# 1_P1.net
KiCad netlist of a schematic drawn in Altium Designer
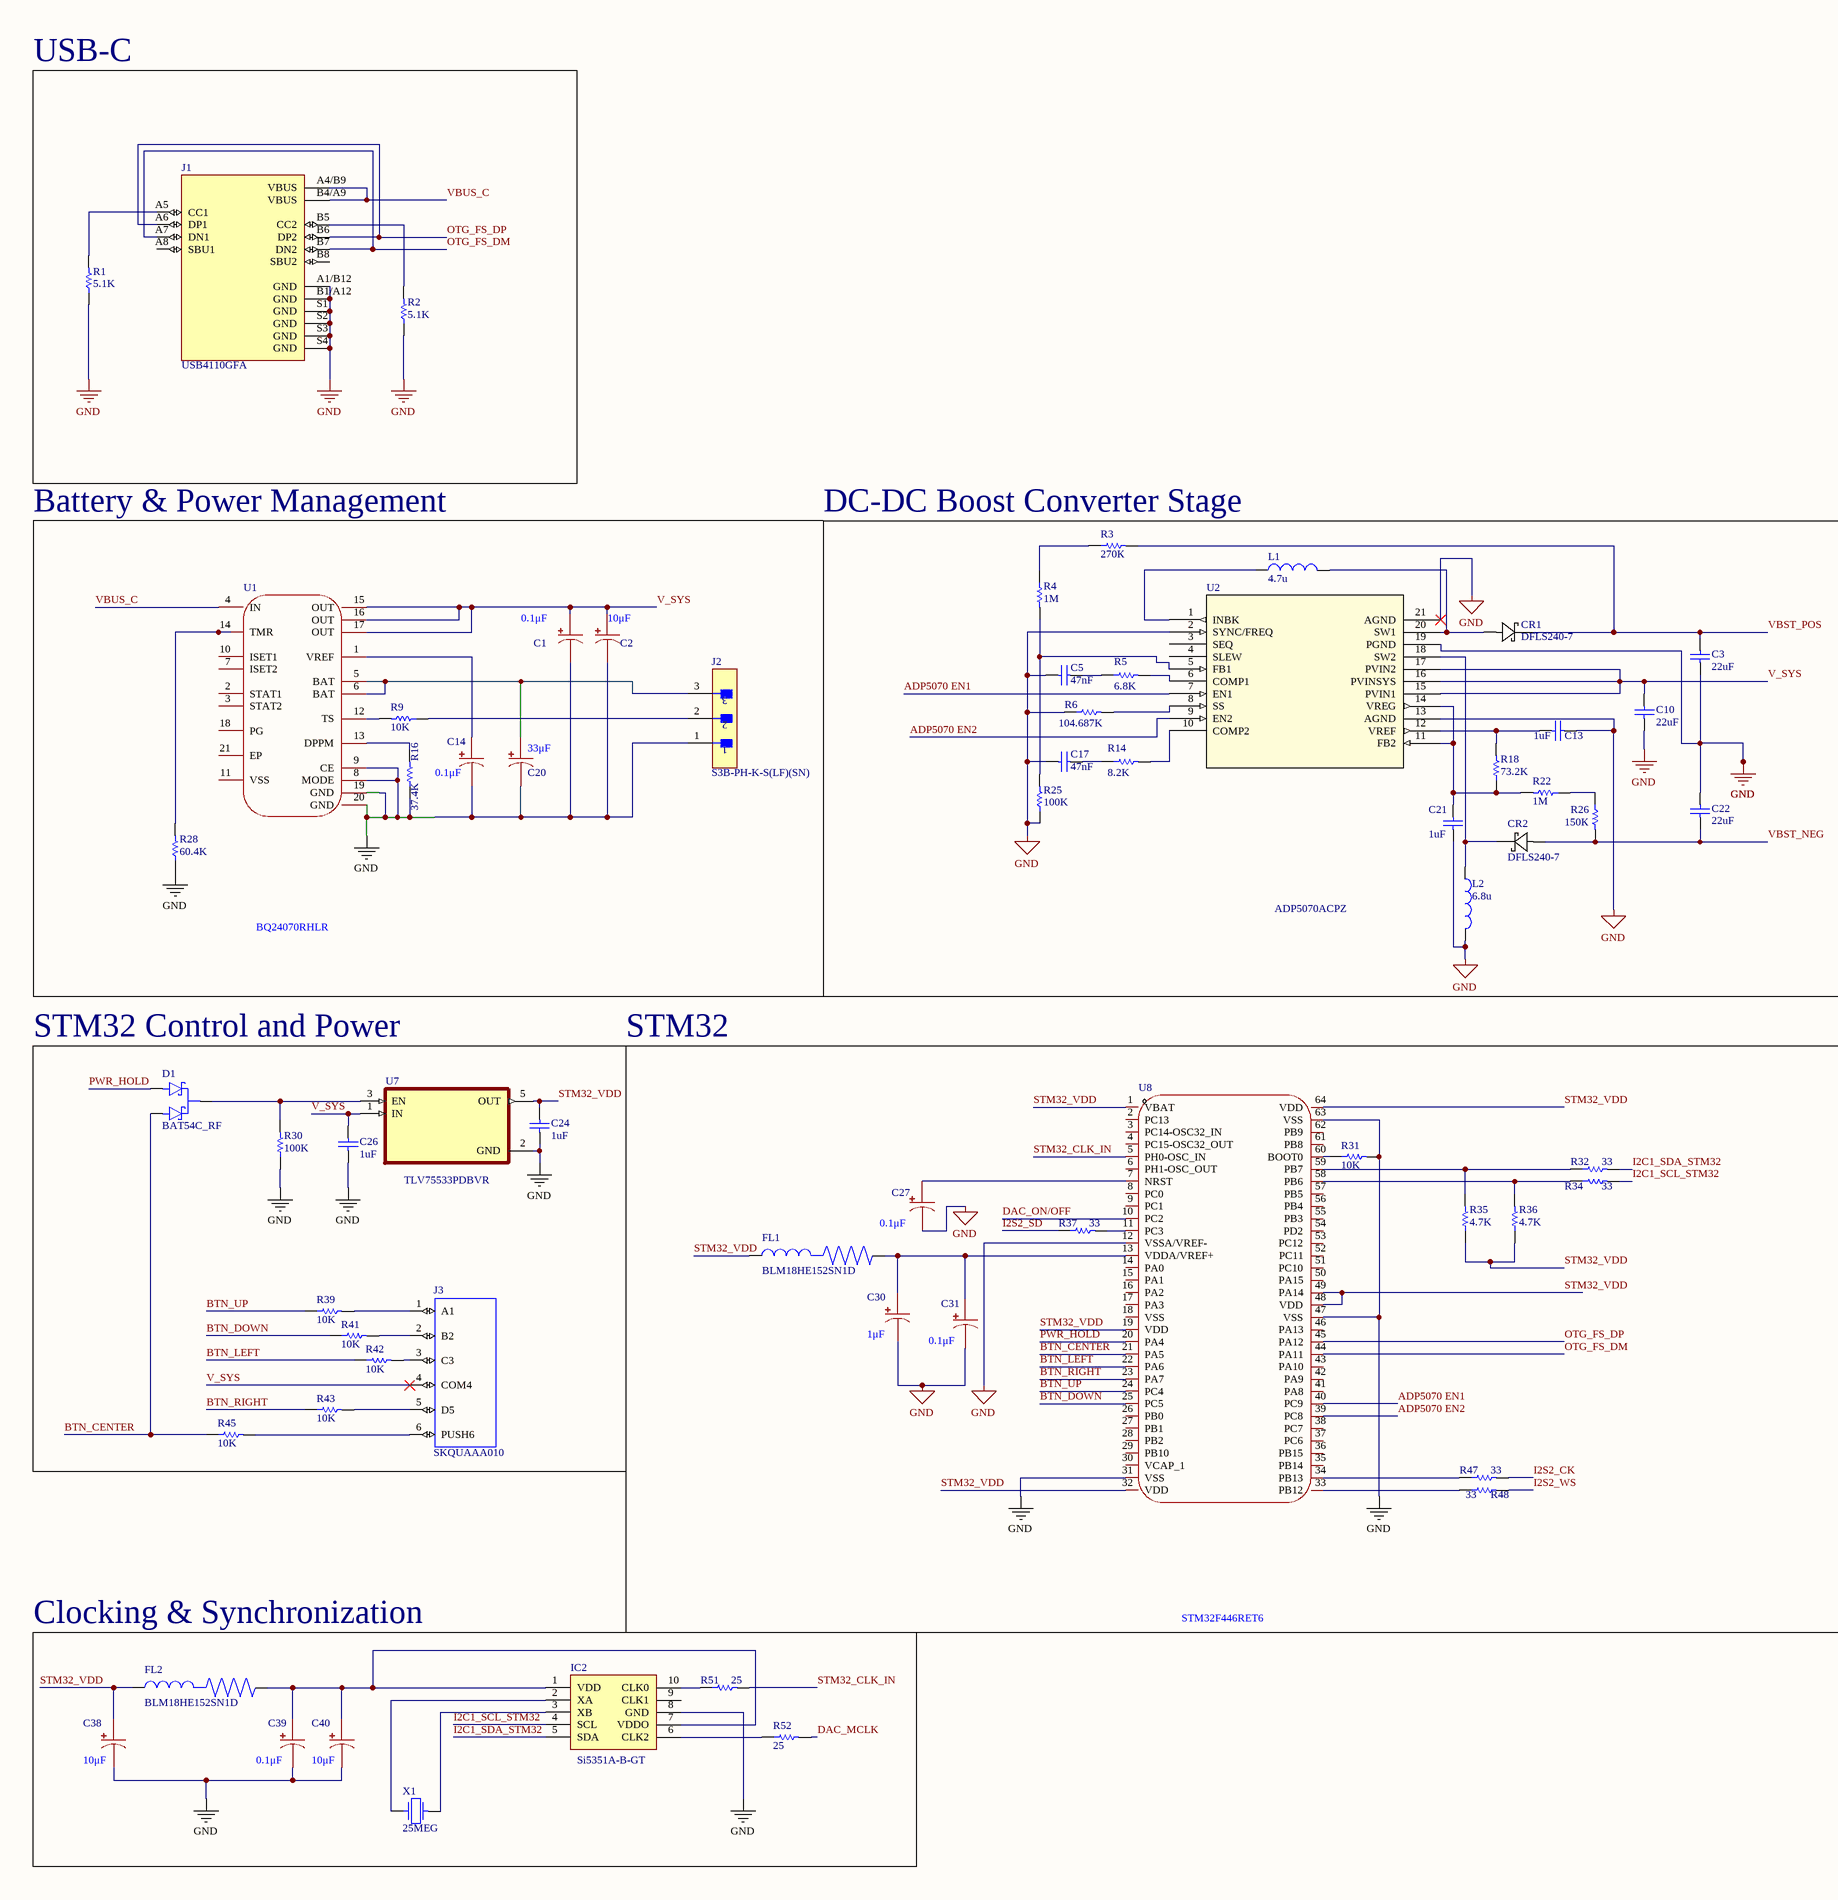
[diagram p0: 1_P1.schdoc, left]
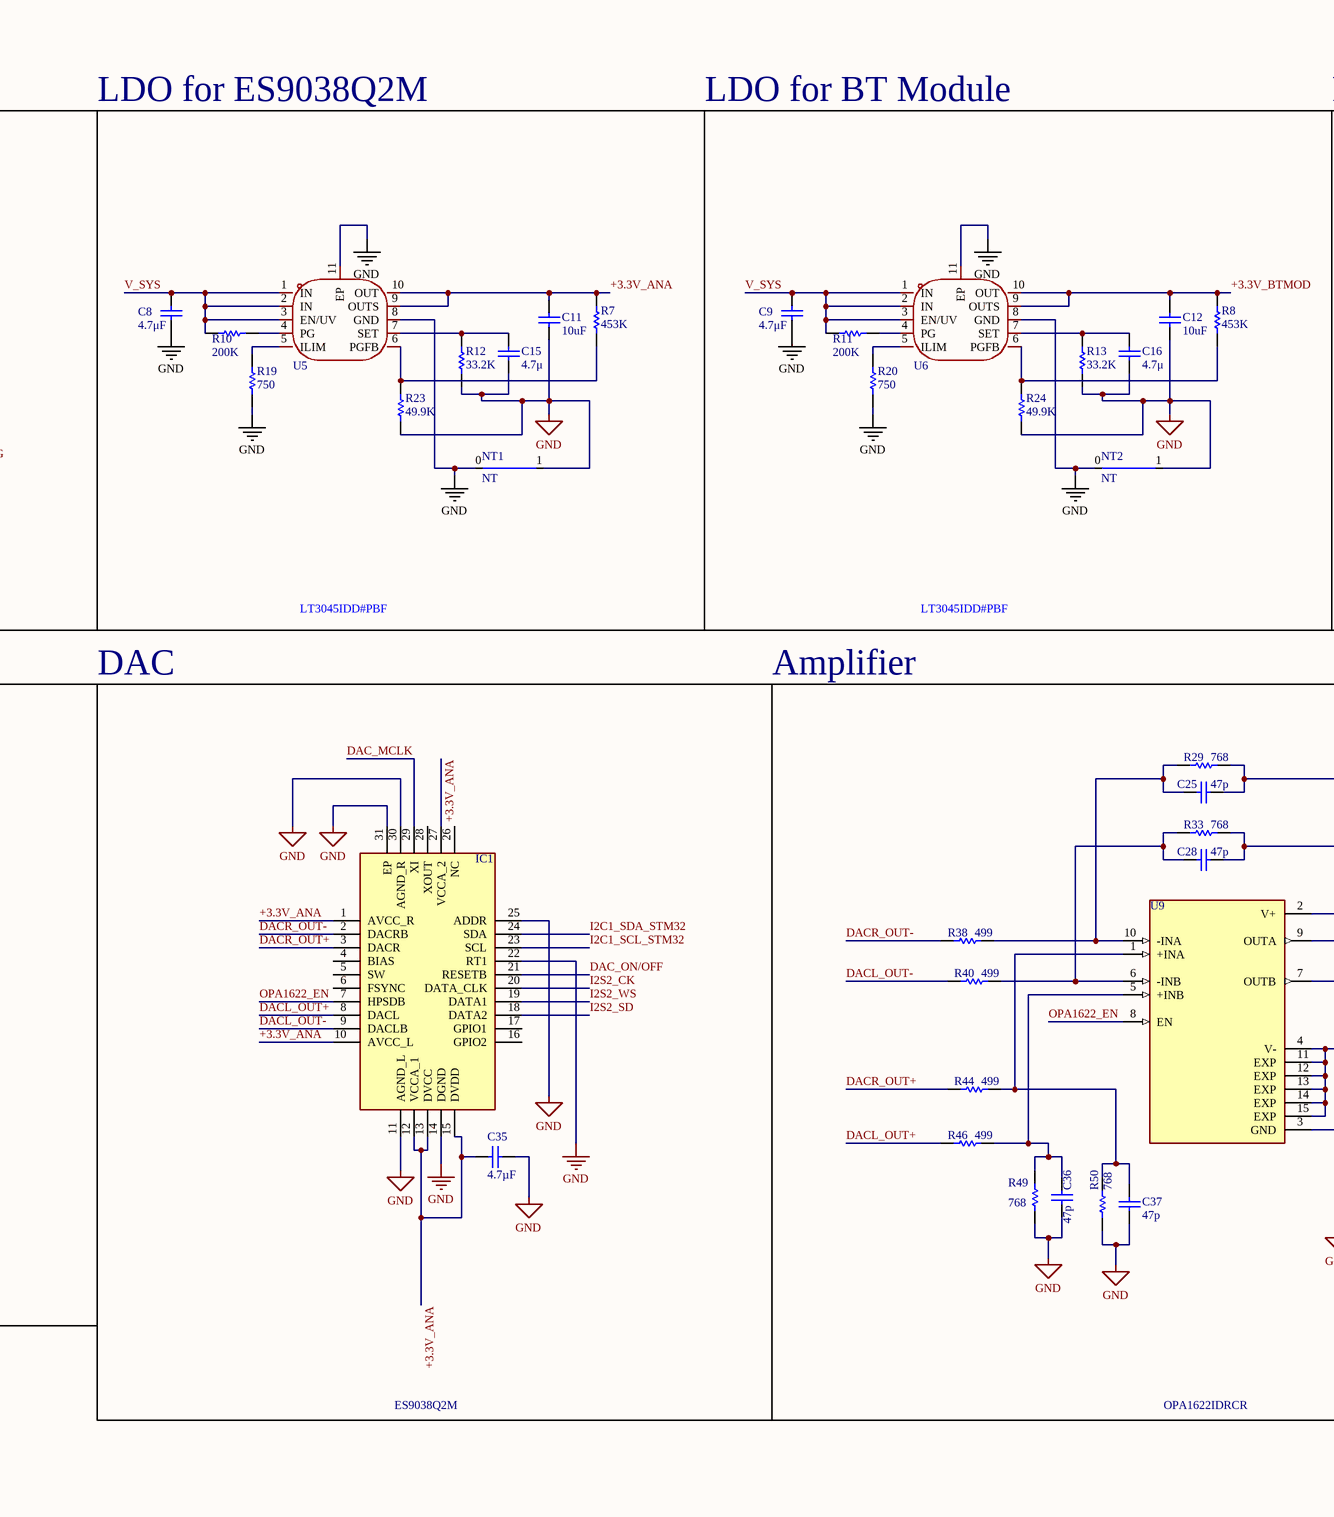
[diagram p1: 1_P1.schdoc, middle]
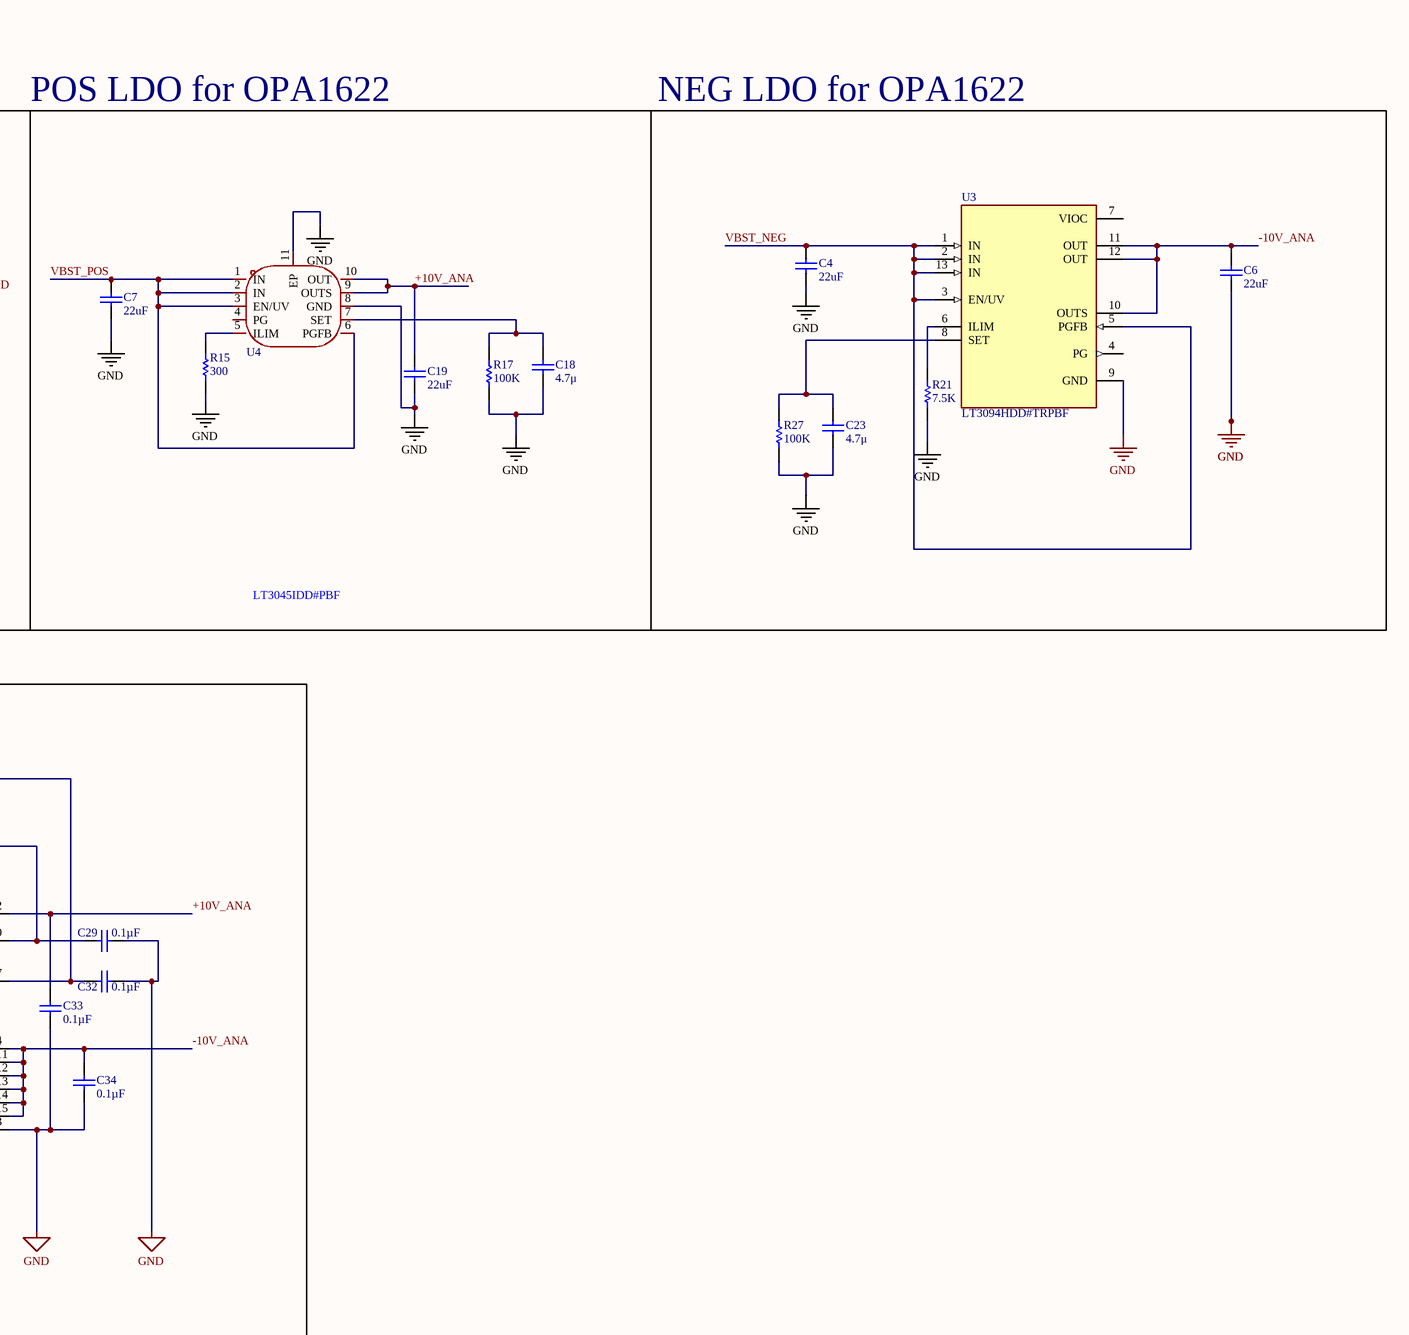
[diagram p2: 1_P1.schdoc, right]

(export (version "E")
  (design (tool "Eeschema 10.0.6"))
  (components
    (comp (ref "C1")
      (value "0.1μF")
      (footprint "FP-GRM155-0_05-MFG")
      (fields
        (field (name "MANUFACTURER") "Nichicon(尼吉康)")
        (field (name "MANUFACTURER PART") "UUG1J101MNQ1MS")
        (field (name "TOLERANCE") "±20%")
      )
      (libsource (lib "altium-import") (part "root_0_UUG1J101MNQ1MS_"))
    )
    (comp (ref "C2")
      (value "10μF")
      (footprint "CAPC2012X145N")
      (fields
        (field (name "MANUFACTURER") "Nichicon(尼吉康)")
        (field (name "MANUFACTURER PART") "UUG1J101MNQ1MS")
        (field (name "TOLERANCE") "±20%")
      )
      (libsource (lib "altium-import") (part "root_0_UUG1J101MNQ1MS_"))
    )
    (comp (ref "C3")
      (value "22uF")
      (footprint "FP-GRM32-MFG")
      (description "Capacitor")
      (libsource (lib "Simulation Generic Components") (part "Capacitor"))
    )
    (comp (ref "C4")
      (value "22uF")
      (footprint "FP-GRM32-MFG")
      (description "Capacitor")
      (libsource (lib "Simulation Generic Components") (part "Capacitor"))
    )
    (comp (ref "C5")
      (value "47nF")
      (footprint "FP-GRM155-0_05-MFG")
      (description "Capacitor")
      (libsource (lib "Simulation Generic Components") (part "Capacitor"))
    )
    (comp (ref "C6")
      (value "22uF")
      (footprint "FP-GRM32-MFG")
      (description "Capacitor")
      (libsource (lib "Simulation Generic Components") (part "Capacitor"))
    )
    (comp (ref "C7")
      (value "22uF")
      (footprint "FP-GRM32-MFG")
      (description "Capacitor")
      (libsource (lib "Simulation Generic Components") (part "Capacitor"))
    )
    (comp (ref "C8")
      (value "4.7μF")
      (footprint "CAPC1608X95N")
      (description "Capacitor")
      (libsource (lib "Simulation Generic Components") (part "Capacitor"))
    )
    (comp (ref "C9")
      (value "4.7μF")
      (footprint "CAPC1608X95N")
      (description "Capacitor")
      (libsource (lib "Simulation Generic Components") (part "Capacitor"))
    )
    (comp (ref "C10")
      (value "22uF")
      (footprint "FP-GRM32-MFG")
      (description "Capacitor")
      (libsource (lib "Simulation Generic Components") (part "Capacitor"))
    )
    (comp (ref "C11")
      (value "10uF")
      (footprint "FP-GRM32-MFG")
      (description "Capacitor")
      (libsource (lib "Simulation Generic Components") (part "Capacitor"))
    )
    (comp (ref "C12")
      (value "10uF")
      (footprint "FP-GRM32-MFG")
      (description "Capacitor")
      (libsource (lib "Simulation Generic Components") (part "Capacitor"))
    )
    (comp (ref "C13")
      (value "1uF")
      (footprint "CAPC1608X90N")
      (description "Capacitor")
      (libsource (lib "Simulation Generic Components") (part "Capacitor"))
    )
    (comp (ref "C14")
      (value "0.1μF")
      (footprint "FP-GRM155-0_05-MFG")
      (fields
        (field (name "MANUFACTURER") "Nichicon(尼吉康)")
        (field (name "MANUFACTURER PART") "UUG1J101MNQ1MS")
        (field (name "TOLERANCE") "±20%")
      )
      (libsource (lib "altium-import") (part "root_0_UUG1J101MNQ1MS_"))
    )
    (comp (ref "C15")
      (value "4.7μ")
      (footprint "FP-CL10-IPC_B")
      (description "Capacitor")
      (libsource (lib "Simulation Generic Components") (part "Capacitor"))
    )
    (comp (ref "C16")
      (value "4.7μ")
      (footprint "FP-CL10-IPC_B")
      (description "Capacitor")
      (libsource (lib "Simulation Generic Components") (part "Capacitor"))
    )
    (comp (ref "C17")
      (value "47nF")
      (footprint "FP-GRM155-0_05-MFG")
      (description "Capacitor")
      (libsource (lib "Simulation Generic Components") (part "Capacitor"))
    )
    (comp (ref "C18")
      (value "4.7μ")
      (footprint "FP-CL10-IPC_B")
      (description "Capacitor")
      (libsource (lib "Simulation Generic Components") (part "Capacitor"))
    )
    (comp (ref "C19")
      (value "22uF")
      (footprint "FP-GRM32-MFG")
      (description "Capacitor")
      (libsource (lib "Simulation Generic Components") (part "Capacitor"))
    )
    (comp (ref "C20")
      (value "33μF")
      (footprint "CAPMP7.6X4.3_3.1N_KEM")
      (fields
        (field (name "MANUFACTURER") "Nichicon(尼吉康)")
        (field (name "MANUFACTURER PART") "UUG1J101MNQ1MS")
        (field (name "TOLERANCE") "±20%")
      )
      (libsource (lib "altium-import") (part "root_0_UUG1J101MNQ1MS_"))
    )
    (comp (ref "C21")
      (value "1uF")
      (footprint "CAPC1608X90N")
      (description "Capacitor")
      (libsource (lib "Simulation Generic Components") (part "Capacitor"))
    )
    (comp (ref "C22")
      (value "22uF")
      (footprint "FP-GRM32-MFG")
      (description "Capacitor")
      (libsource (lib "Simulation Generic Components") (part "Capacitor"))
    )
    (comp (ref "C23")
      (value "4.7μ")
      (footprint "FP-CL10-IPC_B")
      (description "Capacitor")
      (libsource (lib "Simulation Generic Components") (part "Capacitor"))
    )
    (comp (ref "C24")
      (value "1uF")
      (footprint "CAPC1608X90N")
      (description "Capacitor")
      (libsource (lib "Simulation Generic Components") (part "Capacitor"))
    )
    (comp (ref "C25")
      (value "47p")
      (footprint "FP-GCM155-0_05-MFG")
      (description "Capacitor")
      (libsource (lib "Simulation Generic Components") (part "Capacitor"))
    )
    (comp (ref "C26")
      (value "1uF")
      (footprint "CAPC1608X90N")
      (description "Capacitor")
      (libsource (lib "Simulation Generic Components") (part "Capacitor"))
    )
    (comp (ref "C27")
      (value "0.1μF")
      (footprint "FP-GRM155-0_05-MFG")
      (fields
        (field (name "MANUFACTURER") "Nichicon(尼吉康)")
        (field (name "MANUFACTURER PART") "UUG1J101MNQ1MS")
        (field (name "TOLERANCE") "±20%")
      )
      (libsource (lib "altium-import") (part "root_0_UUG1J101MNQ1MS_"))
    )
    (comp (ref "C28")
      (value "47p")
      (footprint "FP-GCM155-0_05-MFG")
      (description "Capacitor")
      (libsource (lib "Simulation Generic Components") (part "Capacitor"))
    )
    (comp (ref "C29")
      (value "0.1µF")
      (footprint "FP-GRM155-0_05-MFG")
      (description "Capacitor")
      (libsource (lib "Simulation Generic Components") (part "Capacitor"))
    )
    (comp (ref "C30")
      (value "1μF")
      (footprint "FP-C0402C-BB-MFG")
      (fields
        (field (name "MANUFACTURER") "Nichicon(尼吉康)")
        (field (name "MANUFACTURER PART") "UUG1J101MNQ1MS")
        (field (name "TOLERANCE") "±20%")
      )
      (libsource (lib "altium-import") (part "root_0_UUG1J101MNQ1MS_"))
    )
    (comp (ref "C31")
      (value "0.1μF")
      (footprint "FP-GRM155-0_05-MFG")
      (fields
        (field (name "MANUFACTURER") "Nichicon(尼吉康)")
        (field (name "MANUFACTURER PART") "UUG1J101MNQ1MS")
        (field (name "TOLERANCE") "±20%")
      )
      (libsource (lib "altium-import") (part "root_0_UUG1J101MNQ1MS_"))
    )
    (comp (ref "C32")
      (value "0.1µF")
      (footprint "FP-GRM155-0_05-MFG")
      (description "Capacitor")
      (libsource (lib "Simulation Generic Components") (part "Capacitor"))
    )
    (comp (ref "C33")
      (value "0.1µF")
      (footprint "FP-GRM155-0_05-MFG")
      (description "Capacitor")
      (libsource (lib "Simulation Generic Components") (part "Capacitor"))
    )
    (comp (ref "C34")
      (value "0.1µF")
      (footprint "FP-GRM155-0_05-MFG")
      (description "Capacitor")
      (libsource (lib "Simulation Generic Components") (part "Capacitor"))
    )
    (comp (ref "C35")
      (value "4.7µF")
      (footprint "FP-CL10-IPC_B")
      (description "Capacitor")
      (libsource (lib "Simulation Generic Components") (part "Capacitor"))
    )
    (comp (ref "C36")
      (value "47p")
      (footprint "FP-GCM155-0_05-MFG")
      (description "Capacitor")
      (libsource (lib "Simulation Generic Components") (part "Capacitor"))
    )
    (comp (ref "C37")
      (value "47p")
      (footprint "FP-GCM155-0_05-MFG")
      (description "Capacitor")
      (libsource (lib "Simulation Generic Components") (part "Capacitor"))
    )
    (comp (ref "C38")
      (value "10μF")
      (footprint "FP-CL21B106KOQNNNE-MFG")
      (fields
        (field (name "MANUFACTURER") "Nichicon(尼吉康)")
        (field (name "MANUFACTURER PART") "UUG1J101MNQ1MS")
        (field (name "TOLERANCE") "±20%")
      )
      (libsource (lib "altium-import") (part "root_0_UUG1J101MNQ1MS_"))
    )
    (comp (ref "C39")
      (value "0.1μF")
      (footprint "FP-GRM155-0_05-MFG")
      (fields
        (field (name "MANUFACTURER") "Nichicon(尼吉康)")
        (field (name "MANUFACTURER PART") "UUG1J101MNQ1MS")
        (field (name "TOLERANCE") "±20%")
      )
      (libsource (lib "altium-import") (part "root_0_UUG1J101MNQ1MS_"))
    )
    (comp (ref "C40")
      (value "10μF")
      (footprint "FP-CL21B106KOQNNNE-MFG")
      (fields
        (field (name "MANUFACTURER") "Nichicon(尼吉康)")
        (field (name "MANUFACTURER PART") "UUG1J101MNQ1MS")
        (field (name "TOLERANCE") "±20%")
      )
      (libsource (lib "altium-import") (part "root_0_UUG1J101MNQ1MS_"))
    )
    (comp (ref "CR1")
      (value "DFLS240-7")
      (footprint "POWERDI123_DIO")
      (description "Description")
      (fields (field (name "COPYRIGHT") "Copyright (C) 2026 Ultra Librarian. All rights reserved."))
      (libsource (lib "DFLS240-7") (part "DFLS240-7"))
    )
    (comp (ref "CR2")
      (value "DFLS240-7")
      (footprint "POWERDI123_DIO")
      (description "Description")
      (fields (field (name "COPYRIGHT") "Copyright (C) 2026 Ultra Librarian. All rights reserved."))
      (libsource (lib "DFLS240-7") (part "DFLS240-7"))
    )
    (comp (ref "D1")
      (value "BAT54C_RF")
      (footprint "SOT95P237X112-3N")
      (description "SOT-23, 30V, 0.2A, Schottky Diode")
      (fields (field (name "MF") "Taiwan Semiconductor") (field (name "MP") "BAT54C RF"))
      (libsource (lib "BAT54C_RF") (part "BAT54C_RF"))
    )
    (comp (ref "FL1")
      (value "BLM18HE152SN1D")
      (footprint "FP-BLM18-0_15-t0_8-MFG")
      (description "1.5 kOhms @ 100MHz 1 Signal Line Ferrite Bead 0603 (1608 Metric) 500mA 500mOhm")
      (fields (field (name "MF") "Murata Electronics"))
      (libsource (lib "BLM18HE152SN1D") (part "BLM18HE152SN1D"))
    )
    (comp (ref "FL2")
      (value "BLM18HE152SN1D")
      (footprint "FP-BLM18-0_15-t0_8-MFG")
      (description "1.5 kOhms @ 100MHz 1 Signal Line Ferrite Bead 0603 (1608 Metric) 500mA 500mOhm")
      (fields (field (name "MF") "Murata Electronics"))
      (libsource (lib "BLM18HE152SN1D") (part "BLM18HE152SN1D"))
    )
    (comp (ref "IC1")
      (value "ES9038Q2M")
      (footprint "SamacSys:QFN40P300X500X80-31N-D")
      (description "Integrated Circuit")
      (fields (field (name "MOUSER PART NUMBER") "460-ES9038Q2M"))
      (libsource (lib "*") (part "ES9038Q2M"))
    )
    (comp (ref "IC2")
      (value "Si5351A-B-GT")
      (footprint "SamacSys:SOP50P490X110-10N")
      (description "Integrated Circuit")
      (fields
        (field (name "MOUSER PART NUMBER") "634-SI5351A-B-GT")
        (field (name "ARROW PART NUMBER") "SI5351A-B-GT")
      )
      (libsource (lib "*") (part "Si5351A-B-GT"))
    )
    (comp (ref "J1")
      (value "USB4110GFA")
      (footprint "GCT_USB4110GFA")
      (fields (field (name "MF") "Global Connector Technology"))
      (libsource (lib "USB4110GFA") (part "USB4110GFA"))
    )
    (comp (ref "J2")
      (value "S3B-PH-K-S(LF)(SN)")
      (footprint "FP-S3B-PH-K-S_LF_SN-MFG")
      (description "CONN HEADER R/A 3POS 2MM")
      (libsource (lib "Altium Content Vault") (part "0d3f023dd272f625e17a2be33dea85f"))
    )
    (comp (ref "J3")
      (value "SKQUAAA010")
      (footprint "SKQUAAA010")
      (libsource (lib "SKQUAAA010") (part "SKQUAAA010"))
    )
    (comp (ref "L1")
      (value "4.7u")
      (footprint "WE-MAPI_4030")
      (description "Inductor")
      (libsource (lib "Simulation Generic Components") (part "Inductor"))
    )
    (comp (ref "L2")
      (value "6.8u")
      (footprint "WE-MAPI_4030")
      (description "Inductor")
      (libsource (lib "Simulation Generic Components") (part "Inductor"))
    )
    (comp (ref "NT1")
      (value "NT")
      (footprint "NETTIE_SMD")
      (description "Net Tie SMD")
      (libsource (lib "Integrated_Library1") (part "NetTie_SMD"))
    )
    (comp (ref "NT2")
      (value "NT")
      (footprint "NETTIE_SMD")
      (description "Net Tie SMD")
      (libsource (lib "Integrated_Library1") (part "NetTie_SMD"))
    )
    (comp (ref "R1")
      (value "5.1K")
      (footprint "RESC1005X40X25NL05T10")
      (description "Resistor")
      (libsource (lib "Simulation Generic Components") (part "Resistor"))
    )
    (comp (ref "R2")
      (value "5.1K")
      (footprint "RESC1005X40X25NL05T10")
      (description "Resistor")
      (libsource (lib "Simulation Generic Components") (part "Resistor"))
    )
    (comp (ref "R3")
      (value "270К")
      (footprint "RES_RS73F_2B_KOA")
      (description "Resistor")
      (libsource (lib "Simulation Generic Components") (part "Resistor"))
    )
    (comp (ref "R4")
      (value "1M")
      (footprint "RESC3216X70X50NL20T25")
      (description "Resistor")
      (libsource (lib "Simulation Generic Components") (part "Resistor"))
    )
    (comp (ref "R5")
      (value "6.8K")
      (footprint "FP-RT0402-MFG")
      (description "Resistor")
      (libsource (lib "Simulation Generic Components") (part "Resistor"))
    )
    (comp (ref "R6")
      (value "104.687K")
      (footprint "SamacSys:ERA2AED122X")
      (description "Resistor")
      (libsource (lib "Simulation Generic Components") (part "Resistor"))
    )
    (comp (ref "R7")
      (value "453K")
      (footprint "SamacSys:ERA2AED122X")
      (description "Resistor")
      (libsource (lib "Simulation Generic Components") (part "Resistor"))
    )
    (comp (ref "R8")
      (value "453K")
      (footprint "SamacSys:ERA2AED122X")
      (description "Resistor")
      (libsource (lib "Simulation Generic Components") (part "Resistor"))
    )
    (comp (ref "R9")
      (value "10K")
      (footprint "RESC1005X40X25NL05T10")
      (description "Resistor")
      (libsource (lib "Simulation Generic Components") (part "Resistor"))
    )
    (comp (ref "R10")
      (value "200K")
      (footprint "RESC1005X40X25NL05T10")
      (description "Resistor")
      (libsource (lib "Simulation Generic Components") (part "Resistor"))
    )
    (comp (ref "R11")
      (value "200K")
      (footprint "RESC1005X40X25NL05T10")
      (description "Resistor")
      (libsource (lib "Simulation Generic Components") (part "Resistor"))
    )
    (comp (ref "R12")
      (value "33.2K")
      (footprint "0402_PAN")
      (description "Resistor")
      (libsource (lib "Simulation Generic Components") (part "Resistor"))
    )
    (comp (ref "R13")
      (value "33.2K")
      (footprint "0402_PAN")
      (description "Resistor")
      (libsource (lib "Simulation Generic Components") (part "Resistor"))
    )
    (comp (ref "R14")
      (value "8.2K")
      (footprint "FP-RT0402-MFG")
      (description "Resistor")
      (libsource (lib "Simulation Generic Components") (part "Resistor"))
    )
    (comp (ref "R15")
      (value "300")
      (footprint "RESC1005X40X25NL10T10")
      (description "Resistor")
      (libsource (lib "Simulation Generic Components") (part "Resistor"))
    )
    (comp (ref "R16")
      (value "37.4K")
      (footprint "0402_PAN")
      (description "Resistor")
      (libsource (lib "Simulation Generic Components") (part "Resistor"))
    )
    (comp (ref "R17")
      (value "100K")
      (footprint "FP-ERA2A-MFG")
      (description "Resistor")
      (libsource (lib "Simulation Generic Components") (part "Resistor"))
    )
    (comp (ref "R18")
      (value "73.2K")
      (footprint "SamacSys:ERA2AED122X")
      (description "Resistor")
      (libsource (lib "Simulation Generic Components") (part "Resistor"))
    )
    (comp (ref "R19")
      (value "750")
      (footprint "RESC1005X40X25NL10T10")
      (description "Resistor")
      (libsource (lib "Simulation Generic Components") (part "Resistor"))
    )
    (comp (ref "R20")
      (value "750")
      (footprint "RESC1005X40X25NL10T10")
      (description "Resistor")
      (libsource (lib "Simulation Generic Components") (part "Resistor"))
    )
    (comp (ref "R21")
      (value "7.5K")
      (footprint "FP-RT0402-MFG")
      (description "Resistor")
      (libsource (lib "Simulation Generic Components") (part "Resistor"))
    )
    (comp (ref "R22")
      (value "1M")
      (footprint "RESC3216X70X50NL20T25")
      (description "Resistor")
      (libsource (lib "Simulation Generic Components") (part "Resistor"))
    )
    (comp (ref "R23")
      (value "49.9K")
      (footprint "0402_PAN")
      (description "Resistor")
      (libsource (lib "Simulation Generic Components") (part "Resistor"))
    )
    (comp (ref "R24")
      (value "49.9K")
      (footprint "0402_PAN")
      (description "Resistor")
      (libsource (lib "Simulation Generic Components") (part "Resistor"))
    )
    (comp (ref "R25")
      (value "100K")
      (footprint "FP-ERA2A-MFG")
      (description "Resistor")
      (libsource (lib "Simulation Generic Components") (part "Resistor"))
    )
    (comp (ref "R26")
      (value "150К")
      (footprint "FP-ERA6A-MFG")
      (description "Resistor")
      (libsource (lib "Simulation Generic Components") (part "Resistor"))
    )
    (comp (ref "R27")
      (value "100K")
      (footprint "FP-ERA2A-MFG")
      (description "Resistor")
      (libsource (lib "Simulation Generic Components") (part "Resistor"))
    )
    (comp (ref "R28")
      (value "60.4K")
      (footprint "RESC1005X40X25NL05T10")
      (description "Resistor")
      (fields (field (name "Comment") "Res_0603"))
      (libsource (lib "Simulation Generic Components") (part "Resistor"))
    )
    (comp (ref "R29")
      (value "768")
      (footprint "SamacSys:ERA2AED122X")
      (description "Resistor")
      (libsource (lib "Simulation Generic Components") (part "Resistor"))
    )
    (comp (ref "R30")
      (value "100K")
      (footprint "FP-ERA2A-MFG")
      (description "Resistor")
      (libsource (lib "Simulation Generic Components") (part "Resistor"))
    )
    (comp (ref "R31")
      (value "10K")
      (footprint "RESC1005X40X25NL05T10")
      (description "Resistor")
      (libsource (lib "Simulation Generic Components") (part "Resistor"))
    )
    (comp (ref "R32")
      (value "33")
      (footprint "FP-RT0402-MFG")
      (description "Resistor")
      (libsource (lib "Simulation Generic Components") (part "Resistor"))
    )
    (comp (ref "R33")
      (value "768")
      (footprint "SamacSys:ERA2AED122X")
      (description "Resistor")
      (libsource (lib "Simulation Generic Components") (part "Resistor"))
    )
    (comp (ref "R34")
      (value "33")
      (footprint "FP-RT0402-MFG")
      (description "Resistor")
      (libsource (lib "Simulation Generic Components") (part "Resistor"))
    )
    (comp (ref "R35")
      (value "4.7K")
      (footprint "RESC1005X40X25NL05T10")
      (description "Resistor")
      (libsource (lib "Simulation Generic Components") (part "Resistor"))
    )
    (comp (ref "R36")
      (value "4.7K")
      (footprint "RESC1005X40X25NL05T10")
      (description "Resistor")
      (libsource (lib "Simulation Generic Components") (part "Resistor"))
    )
    (comp (ref "R37")
      (value "33")
      (footprint "FP-RT0402-MFG")
      (description "Resistor")
      (libsource (lib "Simulation Generic Components") (part "Resistor"))
    )
    (comp (ref "R38")
      (value "499")
      (footprint "0402_PAN")
      (description "Resistor")
      (libsource (lib "Simulation Generic Components") (part "Resistor"))
    )
    (comp (ref "R39")
      (value "10K")
      (footprint "RESC1005X40X25NL05T10")
      (description "Resistor")
      (libsource (lib "Simulation Generic Components") (part "Resistor"))
    )
    (comp (ref "R40")
      (value "499")
      (footprint "0402_PAN")
      (description "Resistor")
      (libsource (lib "Simulation Generic Components") (part "Resistor"))
    )
    (comp (ref "R41")
      (value "10K")
      (footprint "RESC1005X40X25NL05T10")
      (description "Resistor")
      (libsource (lib "Simulation Generic Components") (part "Resistor"))
    )
    (comp (ref "R42")
      (value "10K")
      (footprint "RESC1005X40X25NL05T10")
      (description "Resistor")
      (libsource (lib "Simulation Generic Components") (part "Resistor"))
    )
    (comp (ref "R43")
      (value "10K")
      (footprint "RESC1005X40X25NL05T10")
      (description "Resistor")
      (libsource (lib "Simulation Generic Components") (part "Resistor"))
    )
    (comp (ref "R44")
      (value "499")
      (footprint "0402_PAN")
      (description "Resistor")
      (libsource (lib "Simulation Generic Components") (part "Resistor"))
    )
    (comp (ref "R45")
      (value "10K")
      (footprint "RESC1005X40X25NL05T10")
      (description "Resistor")
      (libsource (lib "Simulation Generic Components") (part "Resistor"))
    )
    (comp (ref "R46")
      (value "499")
      (footprint "0402_PAN")
      (description "Resistor")
      (libsource (lib "Simulation Generic Components") (part "Resistor"))
    )
    (comp (ref "R47")
      (value "33")
      (footprint "FP-RT0402-MFG")
      (description "Resistor")
      (libsource (lib "Simulation Generic Components") (part "Resistor"))
    )
    (comp (ref "R48")
      (value "33")
      (footprint "FP-RT0402-MFG")
      (description "Resistor")
      (libsource (lib "Simulation Generic Components") (part "Resistor"))
    )
    (comp (ref "R49")
      (value "768")
      (footprint "SamacSys:ERA2AED122X")
      (description "Resistor")
      (libsource (lib "Simulation Generic Components") (part "Resistor"))
    )
    (comp (ref "R50")
      (value "768")
      (footprint "SamacSys:ERA2AED122X")
      (description "Resistor")
      (libsource (lib "Simulation Generic Components") (part "Resistor"))
    )
    (comp (ref "R51")
      (value "25")
      (footprint "FP-RT0402-0_35-MFG")
      (description "Resistor")
      (libsource (lib "Simulation Generic Components") (part "Resistor"))
    )
    (comp (ref "R52")
      (value "25")
      (footprint "FP-RT0402-0_35-MFG")
      (description "Resistor")
      (libsource (lib "Simulation Generic Components") (part "Resistor"))
    )
    (comp (ref "U1")
      (value "BQ24070RHLR")
      (footprint "RHL0020A_V")
      (fields (field (name "MANUFACTURER") "TI(德州仪器)"))
      (libsource (lib "altium-import") (part "root_0_BQ24070RHLR_"))
    )
    (comp (ref "U2")
      (value "ADP5070ACPZ")
      (footprint "CP-20-8_ADI")
      (description "1 A/0.6 A, DC-to-DC Switching Regulator with Independent Positive and Negative Outputs")
      (fields (field (name "COPYRIGHT") "Copyright (C) 2025 Ultra Librarian. All rights reserved."))
      (libsource (lib "ADP5070ACPZ") (part "ADP5070ACPZ"))
    )
    (comp (ref "U3")
      (value "LT3094HDD#TRPBF")
      (footprint "SON45P300X300X80-13N")
      (description "âˆ’20V, 500mA, Ultralow Noise, Ultrahigh PSRR Negative Linear Regulator")
      (fields (field (name "MF") "Analog Devices"))
      (libsource (lib "LT3094HDD_TRPBF") (part "LT3094HDD#TRPBF"))
    )
    (comp (ref "U4")
      (value "LT3045IDD#PBF")
      (footprint "FP-DD-10-05-08-1699-MFG")
      (fields (field (name "MANUFACTURER") "ADI(亚德诺)"))
      (libsource (lib "altium-import") (part "root_0_LT3045IDD#PBF_"))
    )
    (comp (ref "U5")
      (value "LT3045IDD#PBF")
      (footprint "FP-DD-10-05-08-1699-MFG")
      (fields (field (name "MANUFACTURER") "ADI(亚德诺)"))
      (libsource (lib "altium-import") (part "root_0_LT3045IDD#PBF_"))
    )
    (comp (ref "U6")
      (value "LT3045IDD#PBF")
      (footprint "FP-DD-10-05-08-1699-MFG")
      (fields (field (name "MANUFACTURER") "ADI(亚德诺)"))
      (libsource (lib "altium-import") (part "root_0_LT3045IDD#PBF_"))
    )
    (comp (ref "U7")
      (value "TLV75533PDBVR")
      (footprint "SOT95P280X145-5N")
      (description "500-mA High-PSRR Low-IQ-Tief-Dropout-Spannungsregler mitablem")
      (fields (field (name "MF") "Texas Instruments"))
      (libsource (lib "TLV75533PDBVR") (part "TLV75533PDBVR"))
    )
    (comp (ref "U8")
      (value "STM32F446RET6")
      (footprint "LQFP64-10x10mm")
      (fields (field (name "MANUFACTURER") "ST(意法半导体)"))
      (libsource (lib "altium-import") (part "root_0_STM32F446RET6_"))
    )
    (comp (ref "U9")
      (value "OPA1622IDRCR")
      (footprint "IC_OPA1622IDRCR")
      (description "SoundPlusâ„¢ Audio Operational Amplifier with High Performance, Low THD+N and Bipolar Input")
      (fields (field (name "MF") "Texas Instruments"))
      (libsource (lib "OPA1622IDRCR") (part "OPA1622IDRCR"))
    )
    (comp (ref "X1")
      (value "Crystal")
      (footprint "FP-NX3225SA-MFG")
      (fields (field (name "F0") "25MEG"))
      (libsource (lib "Simulation Generic Components") (part "Crystal"))
    )
  )
  (nets
    (net (code "1") (name "/+3.3V_ANA") (class "Default")
      (node (ref "C11") (pin "2") (pinfunction "2_2") (pintype "passive"))
      (node (ref "C35") (pin "1") (pinfunction "1_1") (pintype "passive"))
      (node (ref "IC1") (pin "1") (pinfunction "AVCC_R_1") (pintype "passive"))
      (node (ref "IC1") (pin "10") (pinfunction "AVCC_L_10") (pintype "passive"))
      (node (ref "IC1") (pin "12") (pinfunction "VCCA_1_12") (pintype "passive"))
      (node (ref "IC1") (pin "13") (pinfunction "DVCC_13") (pintype "passive"))
      (node (ref "IC1") (pin "15") (pinfunction "DVDD_15") (pintype "passive"))
      (node (ref "IC1") (pin "27") (pinfunction "VCCA_2_27") (pintype "passive"))
      (node (ref "R7") (pin "2") (pinfunction "2_2") (pintype "passive"))
      (node (ref "U5") (pin "10") (pinfunction "OUT_10") (pintype "passive"))
      (node (ref "U5") (pin "9") (pinfunction "OUTS_9") (pintype "passive"))
    )
    (net (code "2") (name "/+3.3V_BTMOD") (class "Default")
      (node (ref "C12") (pin "2") (pinfunction "2_2") (pintype "passive"))
      (node (ref "R8") (pin "2") (pinfunction "2_2") (pintype "passive"))
      (node (ref "U6") (pin "10") (pinfunction "OUT_10") (pintype "passive"))
      (node (ref "U6") (pin "9") (pinfunction "OUTS_9") (pintype "passive"))
    )
    (net (code "3") (name "/+10V_ANA") (class "Default")
      (node (ref "C19") (pin "2") (pinfunction "2_2") (pintype "passive"))
      (node (ref "C33") (pin "2") (pinfunction "2_2") (pintype "passive"))
      (node (ref "U4") (pin "10") (pinfunction "OUT_10") (pintype "passive"))
      (node (ref "U4") (pin "9") (pinfunction "OUTS_9") (pintype "passive"))
      (node (ref "U9") (pin "2") (pinfunction "V+_2") (pintype "power_in"))
    )
    (net (code "4") (name "/-10V_ANA") (class "Default")
      (node (ref "C34") (pin "2") (pinfunction "2_2") (pintype "passive"))
      (node (ref "C6") (pin "2") (pinfunction "2_2") (pintype "passive"))
      (node (ref "U3") (pin "10") (pinfunction "OUTS_10") (pintype "passive"))
      (node (ref "U3") (pin "11") (pinfunction "OUT_11") (pintype "passive"))
      (node (ref "U3") (pin "12") (pinfunction "OUT_12") (pintype "passive"))
      (node (ref "U9") (pin "11") (pinfunction "EXP_11") (pintype "power_in"))
      (node (ref "U9") (pin "12") (pinfunction "EXP_12") (pintype "power_in"))
      (node (ref "U9") (pin "13") (pinfunction "EXP_13") (pintype "power_in"))
      (node (ref "U9") (pin "14") (pinfunction "EXP_14") (pintype "power_in"))
      (node (ref "U9") (pin "15") (pinfunction "EXP_15") (pintype "power_in"))
      (node (ref "U9") (pin "4") (pinfunction "V-_4") (pintype "power_in"))
    )
    (net (code "5") (name "/ADP5070 EN1") (class "Default")
      (node (ref "U2") (pin "7") (pinfunction "EN1_7") (pintype "input"))
      (node (ref "U8") (pin "40") (pinfunction "PC9_40") (pintype "passive"))
    )
    (net (code "6") (name "/ADP5070 EN2") (class "Default")
      (node (ref "U2") (pin "9") (pinfunction "EN2_9") (pintype "input"))
      (node (ref "U8") (pin "39") (pinfunction "PC8_39") (pintype "passive"))
    )
    (net (code "7") (name "/BTN_CENTER") (class "Default")
      (node (ref "D1") (pin "2") (pinfunction "2_2") (pintype "passive"))
      (node (ref "R45") (pin "1") (pinfunction "1_1") (pintype "passive"))
      (node (ref "U8") (pin "21") (pinfunction "PA5_21") (pintype "passive"))
    )
    (net (code "8") (name "/BTN_DOWN") (class "Default")
      (node (ref "R41") (pin "1") (pinfunction "1_1") (pintype "passive"))
      (node (ref "U8") (pin "25") (pinfunction "PC5_25") (pintype "passive"))
    )
    (net (code "9") (name "/BTN_LEFT") (class "Default")
      (node (ref "R42") (pin "1") (pinfunction "1_1") (pintype "passive"))
      (node (ref "U8") (pin "22") (pinfunction "PA6_22") (pintype "passive"))
    )
    (net (code "10") (name "/BTN_RIGHT") (class "Default")
      (node (ref "R43") (pin "1") (pinfunction "1_1") (pintype "passive"))
      (node (ref "U8") (pin "23") (pinfunction "PA7_23") (pintype "passive"))
    )
    (net (code "11") (name "/BTN_UP") (class "Default")
      (node (ref "R39") (pin "1") (pinfunction "1_1") (pintype "passive"))
      (node (ref "U8") (pin "24") (pinfunction "PC4_24") (pintype "passive"))
    )
    (net (code "12") (name "/DACL_OUT+") (class "Default")
      (node (ref "IC1") (pin "8") (pinfunction "DACL_8") (pintype "passive"))
      (node (ref "R46") (pin "1") (pinfunction "1_1") (pintype "passive"))
    )
    (net (code "13") (name "/DACL_OUT-") (class "Default")
      (node (ref "IC1") (pin "9") (pinfunction "DACLB_9") (pintype "passive"))
      (node (ref "R40") (pin "1") (pinfunction "1_1") (pintype "passive"))
    )
    (net (code "14") (name "/DACR_OUT+") (class "Default")
      (node (ref "IC1") (pin "3") (pinfunction "DACR_3") (pintype "passive"))
      (node (ref "R44") (pin "1") (pinfunction "1_1") (pintype "passive"))
    )
    (net (code "15") (name "/DACR_OUT-") (class "Default")
      (node (ref "IC1") (pin "2") (pinfunction "DACRB_2") (pintype "passive"))
      (node (ref "R38") (pin "1") (pinfunction "1_1") (pintype "passive"))
    )
    (net (code "16") (name "/DAC_MCLK") (class "Default")
      (node (ref "IC1") (pin "29") (pinfunction "XI_29") (pintype "passive"))
      (node (ref "R52") (pin "2") (pinfunction "2_2") (pintype "passive"))
    )
    (net (code "17") (name "/DAC_ON{slash}OFF") (class "Default")
      (node (ref "IC1") (pin "21") (pinfunction "RESETB_21") (pintype "passive"))
      (node (ref "U8") (pin "10") (pinfunction "PC2_10") (pintype "passive"))
    )
    (net (code "18") (name "/I2C1_SCL_STM32") (class "Default")
      (node (ref "IC1") (pin "23") (pinfunction "SCL_23") (pintype "passive"))
      (node (ref "IC2") (pin "4") (pinfunction "SCL_4") (pintype "passive"))
      (node (ref "R34") (pin "2") (pinfunction "2_2") (pintype "passive"))
    )
    (net (code "19") (name "/I2C1_SDA_STM32") (class "Default")
      (node (ref "IC1") (pin "24") (pinfunction "SDA_24") (pintype "passive"))
      (node (ref "IC2") (pin "5") (pinfunction "SDA_5") (pintype "passive"))
      (node (ref "R32") (pin "2") (pinfunction "2_2") (pintype "passive"))
    )
    (net (code "20") (name "/I2S2_CK") (class "Default")
      (node (ref "IC1") (pin "20") (pinfunction "DATA_CLK_20") (pintype "passive"))
      (node (ref "R47") (pin "2") (pinfunction "2_2") (pintype "passive"))
    )
    (net (code "21") (name "/I2S2_SD") (class "Default")
      (node (ref "IC1") (pin "18") (pinfunction "DATA2_18") (pintype "passive"))
      (node (ref "R37") (pin "1") (pinfunction "1_1") (pintype "passive"))
    )
    (net (code "22") (name "/I2S2_WS") (class "Default")
      (node (ref "IC1") (pin "19") (pinfunction "DATA1_19") (pintype "passive"))
      (node (ref "R48") (pin "2") (pinfunction "2_2") (pintype "passive"))
    )
    (net (code "23") (name "/OPA1622_EN") (class "Default")
      (node (ref "IC1") (pin "7") (pinfunction "HPSDB_7") (pintype "passive"))
      (node (ref "U9") (pin "8") (pinfunction "EN_8") (pintype "input"))
    )
    (net (code "24") (name "/OTG_FS_DM") (class "Default")
      (node (ref "J1") (pin "A7") (pinfunction "DN1_A7") (pintype "bidirectional"))
      (node (ref "J1") (pin "B7") (pinfunction "DN2_B7") (pintype "bidirectional"))
      (node (ref "U8") (pin "44") (pinfunction "PA11_44") (pintype "passive"))
    )
    (net (code "25") (name "/OTG_FS_DP") (class "Default")
      (node (ref "J1") (pin "A6") (pinfunction "DP1_A6") (pintype "bidirectional"))
      (node (ref "J1") (pin "B6") (pinfunction "DP2_B6") (pintype "bidirectional"))
      (node (ref "U8") (pin "45") (pinfunction "PA12_45") (pintype "passive"))
    )
    (net (code "26") (name "/PWR_HOLD") (class "Default")
      (node (ref "D1") (pin "1") (pinfunction "1_1") (pintype "passive"))
      (node (ref "U8") (pin "20") (pinfunction "PA4_20") (pintype "passive"))
    )
    (net (code "27") (name "/STM32_CLK_IN") (class "Default")
      (node (ref "R51") (pin "2") (pinfunction "2_2") (pintype "passive"))
      (node (ref "U8") (pin "5") (pinfunction "PH0-OSC_IN_5") (pintype "passive"))
    )
    (net (code "28") (name "/STM32_VDD") (class "Default")
      (node (ref "C24") (pin "2") (pinfunction "2_2") (pintype "passive"))
      (node (ref "C38") (pin "1") (pinfunction "1_1") (pintype "passive"))
      (node (ref "FL1") (pin "1") (pinfunction "1_1") (pintype "passive"))
      (node (ref "FL2") (pin "1") (pinfunction "1_1") (pintype "passive"))
      (node (ref "R35") (pin "1") (pinfunction "1_1") (pintype "passive"))
      (node (ref "R36") (pin "1") (pinfunction "1_1") (pintype "passive"))
      (node (ref "U7") (pin "5") (pinfunction "OUT_5") (pintype "output"))
      (node (ref "U8") (pin "1") (pinfunction "VBAT_1") (pintype "passive"))
      (node (ref "U8") (pin "19") (pinfunction "VDD_19") (pintype "passive"))
      (node (ref "U8") (pin "32") (pinfunction "VDD_32") (pintype "passive"))
      (node (ref "U8") (pin "48") (pinfunction "VDD_48") (pintype "passive"))
      (node (ref "U8") (pin "49") (pinfunction "PA14_49") (pintype "passive"))
      (node (ref "U8") (pin "64") (pinfunction "VDD_64") (pintype "passive"))
    )
    (net (code "29") (name "/VBST_NEG") (class "Default")
      (node (ref "C22") (pin "2") (pinfunction "2_2") (pintype "passive"))
      (node (ref "C4") (pin "2") (pinfunction "2_2") (pintype "passive"))
      (node (ref "CR2") (pin "2") (pinfunction "2_2") (pintype "passive"))
      (node (ref "R26") (pin "2") (pinfunction "2_2") (pintype "passive"))
      (node (ref "U3") (pin "1") (pinfunction "IN_1") (pintype "input"))
      (node (ref "U3") (pin "13") (pinfunction "IN_13") (pintype "input"))
      (node (ref "U3") (pin "2") (pinfunction "IN_2") (pintype "input"))
      (node (ref "U3") (pin "3") (pinfunction "EN/UV_3") (pintype "input"))
      (node (ref "U3") (pin "5") (pinfunction "PGFB_5") (pintype "input"))
    )
    (net (code "30") (name "/VBST_POS") (class "Default")
      (node (ref "C3") (pin "1") (pinfunction "1_1") (pintype "passive"))
      (node (ref "C7") (pin "2") (pinfunction "2_2") (pintype "passive"))
      (node (ref "CR1") (pin "1") (pinfunction "1_1") (pintype "passive"))
      (node (ref "R3") (pin "2") (pinfunction "2_2") (pintype "passive"))
      (node (ref "U4") (pin "1") (pinfunction "IN_1") (pintype "passive"))
      (node (ref "U4") (pin "2") (pinfunction "IN_2") (pintype "passive"))
      (node (ref "U4") (pin "3") (pinfunction "EN/UV_3") (pintype "passive"))
      (node (ref "U4") (pin "6") (pinfunction "PGFB_6") (pintype "passive"))
    )
    (net (code "31") (name "/VBUS_C") (class "Default")
      (node (ref "J1") (pin "A4/B9") (pinfunction "VBUS_A4/B9") (pintype "power_in"))
      (node (ref "J1") (pin "B4/A9") (pinfunction "VBUS_B4/A9") (pintype "power_in"))
      (node (ref "U1") (pin "4") (pinfunction "IN_4") (pintype "passive"))
    )
    (net (code "32") (name "/V_SYS") (class "Default")
      (node (ref "C1") (pin "1") (pinfunction "1_1") (pintype "passive"))
      (node (ref "C10") (pin "1") (pinfunction "1_1") (pintype "passive"))
      (node (ref "C2") (pin "1") (pinfunction "1_1") (pintype "passive"))
      (node (ref "C26") (pin "2") (pinfunction "2_2") (pintype "passive"))
      (node (ref "C8") (pin "2") (pinfunction "2_2") (pintype "passive"))
      (node (ref "C9") (pin "2") (pinfunction "2_2") (pintype "passive"))
      (node (ref "J3") (pin "4") (pinfunction "COM4_4") (pintype "bidirectional"))
      (node (ref "R10") (pin "1") (pinfunction "1_1") (pintype "passive"))
      (node (ref "R11") (pin "1") (pinfunction "1_1") (pintype "passive"))
      (node (ref "U1") (pin "15") (pinfunction "OUT_15") (pintype "passive"))
      (node (ref "U1") (pin "16") (pinfunction "OUT_16") (pintype "passive"))
      (node (ref "U1") (pin "17") (pinfunction "OUT_17") (pintype "passive"))
      (node (ref "U2") (pin "15") (pinfunction "PVIN1_15") (pintype "power_in"))
      (node (ref "U2") (pin "16") (pinfunction "PVINSYS_16") (pintype "power_in"))
      (node (ref "U2") (pin "17") (pinfunction "PVIN2_17") (pintype "power_in"))
      (node (ref "U5") (pin "1") (pinfunction "IN_1") (pintype "passive"))
      (node (ref "U5") (pin "2") (pinfunction "IN_2") (pintype "passive"))
      (node (ref "U5") (pin "3") (pinfunction "EN/UV_3") (pintype "passive"))
      (node (ref "U6") (pin "1") (pinfunction "IN_1") (pintype "passive"))
      (node (ref "U6") (pin "2") (pinfunction "IN_2") (pintype "passive"))
      (node (ref "U6") (pin "3") (pinfunction "EN/UV_3") (pintype "passive"))
      (node (ref "U7") (pin "1") (pinfunction "IN_1") (pintype "input"))
    )
    (net (code "33") (name "GND") (class "Default")
      (node (ref "C1") (pin "2") (pinfunction "2_2") (pintype "passive"))
      (node (ref "C10") (pin "2") (pinfunction "2_2") (pintype "passive"))
      (node (ref "C11") (pin "1") (pinfunction "1_1") (pintype "passive"))
      (node (ref "C12") (pin "1") (pinfunction "1_1") (pintype "passive"))
      (node (ref "C13") (pin "2") (pinfunction "2_2") (pintype "passive"))
      (node (ref "C14") (pin "2") (pinfunction "2_2") (pintype "passive"))
      (node (ref "C15") (pin "1") (pinfunction "1_1") (pintype "passive"))
      (node (ref "C16") (pin "1") (pinfunction "1_1") (pintype "passive"))
      (node (ref "C17") (pin "1") (pinfunction "1_1") (pintype "passive"))
      (node (ref "C18") (pin "1") (pinfunction "1_1") (pintype "passive"))
      (node (ref "C19") (pin "1") (pinfunction "1_1") (pintype "passive"))
      (node (ref "C2") (pin "2") (pinfunction "2_2") (pintype "passive"))
      (node (ref "C20") (pin "2") (pinfunction "2_2") (pintype "passive"))
      (node (ref "C21") (pin "2") (pinfunction "2_2") (pintype "passive"))
      (node (ref "C22") (pin "1") (pinfunction "1_1") (pintype "passive"))
      (node (ref "C23") (pin "1") (pinfunction "1_1") (pintype "passive"))
      (node (ref "C24") (pin "1") (pinfunction "1_1") (pintype "passive"))
      (node (ref "C26") (pin "1") (pinfunction "1_1") (pintype "passive"))
      (node (ref "C27") (pin "2") (pinfunction "2_2") (pintype "passive"))
      (node (ref "C29") (pin "2") (pinfunction "2_2") (pintype "passive"))
      (node (ref "C3") (pin "2") (pinfunction "2_2") (pintype "passive"))
      (node (ref "C30") (pin "2") (pinfunction "2_2") (pintype "passive"))
      (node (ref "C31") (pin "2") (pinfunction "2_2") (pintype "passive"))
      (node (ref "C32") (pin "2") (pinfunction "2_2") (pintype "passive"))
      (node (ref "C33") (pin "1") (pinfunction "1_1") (pintype "passive"))
      (node (ref "C34") (pin "1") (pinfunction "1_1") (pintype "passive"))
      (node (ref "C35") (pin "2") (pinfunction "2_2") (pintype "passive"))
      (node (ref "C36") (pin "1") (pinfunction "1_1") (pintype "passive"))
      (node (ref "C37") (pin "1") (pinfunction "1_1") (pintype "passive"))
      (node (ref "C38") (pin "2") (pinfunction "2_2") (pintype "passive"))
      (node (ref "C39") (pin "2") (pinfunction "2_2") (pintype "passive"))
      (node (ref "C4") (pin "1") (pinfunction "1_1") (pintype "passive"))
      (node (ref "C40") (pin "2") (pinfunction "2_2") (pintype "passive"))
      (node (ref "C5") (pin "1") (pinfunction "1_1") (pintype "passive"))
      (node (ref "C6") (pin "1") (pinfunction "1_1") (pintype "passive"))
      (node (ref "C7") (pin "1") (pinfunction "1_1") (pintype "passive"))
      (node (ref "C8") (pin "1") (pinfunction "1_1") (pintype "passive"))
      (node (ref "C9") (pin "1") (pinfunction "1_1") (pintype "passive"))
      (node (ref "IC1") (pin "11") (pinfunction "AGND_L_11") (pintype "passive"))
      (node (ref "IC1") (pin "14") (pinfunction "DGND_14") (pintype "passive"))
      (node (ref "IC1") (pin "22") (pinfunction "RT1_22") (pintype "passive"))
      (node (ref "IC1") (pin "25") (pinfunction "ADDR_25") (pintype "passive"))
      (node (ref "IC1") (pin "30") (pinfunction "AGND_R_30") (pintype "passive"))
      (node (ref "IC1") (pin "31") (pinfunction "EP_31") (pintype "passive"))
      (node (ref "IC2") (pin "8") (pinfunction "GND_8") (pintype "passive"))
      (node (ref "J1") (pin "A1/B12") (pinfunction "GND_A1/B12") (pintype "power_in"))
      (node (ref "J1") (pin "B1/A12") (pinfunction "GND_B1/A12") (pintype "power_in"))
      (node (ref "J1") (pin "S1") (pinfunction "GND_S1") (pintype "power_in"))
      (node (ref "J1") (pin "S2") (pinfunction "GND_S2") (pintype "power_in"))
      (node (ref "J1") (pin "S3") (pinfunction "GND_S3") (pintype "power_in"))
      (node (ref "J1") (pin "S4") (pinfunction "GND_S4") (pintype "power_in"))
      (node (ref "J2") (pin "1") (pinfunction "1_1") (pintype "passive"))
      (node (ref "L2") (pin "2") (pinfunction "2_2") (pintype "passive"))
      (node (ref "NT1") (pin "0") (pinfunction "0_0") (pintype "passive"))
      (node (ref "NT1") (pin "1") (pinfunction "1_1") (pintype "passive"))
      (node (ref "NT2") (pin "0") (pinfunction "0_0") (pintype "passive"))
      (node (ref "NT2") (pin "1") (pinfunction "1_1") (pintype "passive"))
      (node (ref "R1") (pin "1") (pinfunction "1_1") (pintype "passive"))
      (node (ref "R12") (pin "1") (pinfunction "1_1") (pintype "passive"))
      (node (ref "R13") (pin "1") (pinfunction "1_1") (pintype "passive"))
      (node (ref "R15") (pin "1") (pinfunction "1_1") (pintype "passive"))
      (node (ref "R16") (pin "1") (pinfunction "1_1") (pintype "passive"))
      (node (ref "R17") (pin "1") (pinfunction "1_1") (pintype "passive"))
      (node (ref "R19") (pin "1") (pinfunction "1_1") (pintype "passive"))
      (node (ref "R2") (pin "1") (pinfunction "1_1") (pintype "passive"))
      (node (ref "R20") (pin "1") (pinfunction "1_1") (pintype "passive"))
      (node (ref "R21") (pin "1") (pinfunction "1_1") (pintype "passive"))
      (node (ref "R23") (pin "1") (pinfunction "1_1") (pintype "passive"))
      (node (ref "R24") (pin "1") (pinfunction "1_1") (pintype "passive"))
      (node (ref "R25") (pin "1") (pinfunction "1_1") (pintype "passive"))
      (node (ref "R27") (pin "1") (pinfunction "1_1") (pintype "passive"))
      (node (ref "R28") (pin "1") (pinfunction "1_1") (pintype "passive"))
      (node (ref "R30") (pin "1") (pinfunction "1_1") (pintype "passive"))
      (node (ref "R31") (pin "2") (pinfunction "2_2") (pintype "passive"))
      (node (ref "R49") (pin "1") (pinfunction "1_1") (pintype "passive"))
      (node (ref "R50") (pin "1") (pinfunction "1_1") (pintype "passive"))
      (node (ref "R6") (pin "1") (pinfunction "1_1") (pintype "passive"))
      (node (ref "U1") (pin "19") (pinfunction "GND_19") (pintype "passive"))
      (node (ref "U1") (pin "20") (pinfunction "GND_20") (pintype "passive"))
      (node (ref "U1") (pin "8") (pinfunction "MODE_8") (pintype "passive"))
      (node (ref "U1") (pin "9") (pinfunction "CE_9") (pintype "passive"))
      (node (ref "U2") (pin "13") (pinfunction "AGND_13") (pintype "power_in"))
      (node (ref "U2") (pin "19") (pinfunction "PGND_19") (pintype "power_in"))
      (node (ref "U2") (pin "2") (pinfunction "SYNC/FREQ_2") (pintype "input"))
      (node (ref "U2") (pin "21") (pinfunction "AGND_21") (pintype "power_in"))
      (node (ref "U3") (pin "9") (pinfunction "GND_9") (pintype "power_in"))
      (node (ref "U4") (pin "11") (pinfunction "EP_11") (pintype "passive"))
      (node (ref "U4") (pin "8") (pinfunction "GND_8") (pintype "passive"))
      (node (ref "U5") (pin "11") (pinfunction "EP_11") (pintype "passive"))
      (node (ref "U5") (pin "8") (pinfunction "GND_8") (pintype "passive"))
      (node (ref "U6") (pin "11") (pinfunction "EP_11") (pintype "passive"))
      (node (ref "U6") (pin "8") (pinfunction "GND_8") (pintype "passive"))
      (node (ref "U7") (pin "2") (pinfunction "GND_2") (pintype "power_in"))
      (node (ref "U8") (pin "12") (pinfunction "VSSA/VREF-_12") (pintype "passive"))
      (node (ref "U8") (pin "31") (pinfunction "VSS_31") (pintype "passive"))
      (node (ref "U8") (pin "47") (pinfunction "VSS_47") (pintype "passive"))
      (node (ref "U8") (pin "63") (pinfunction "VSS_63") (pintype "passive"))
      (node (ref "U9") (pin "3") (pinfunction "GND_3") (pintype "power_in"))
    )
    (net (code "34") (name "Net-(C5-Pad2)") (class "Default")
      (node (ref "C5") (pin "2") (pinfunction "2_2") (pintype "passive"))
      (node (ref "R5") (pin "1") (pinfunction "1_1") (pintype "passive"))
    )
    (net (code "35") (name "Net-(C17-Pad2)") (class "Default")
      (node (ref "C17") (pin "2") (pinfunction "2_2") (pintype "passive"))
      (node (ref "R14") (pin "1") (pinfunction "1_1") (pintype "passive"))
    )
    (net (code "36") (name "Net-(C20-Pad1)") (class "Default")
      (node (ref "C20") (pin "1") (pinfunction "1_1") (pintype "passive"))
      (node (ref "J2") (pin "3") (pinfunction "3_3") (pintype "passive"))
      (node (ref "U1") (pin "5") (pinfunction "BAT_5") (pintype "passive"))
      (node (ref "U1") (pin "6") (pinfunction "BAT_6") (pintype "passive"))
    )
    (net (code "37") (name "Net-(IC2-CLK0)") (class "Default")
      (node (ref "IC2") (pin "10") (pinfunction "CLK0_10") (pintype "passive"))
      (node (ref "R51") (pin "1") (pinfunction "1_1") (pintype "passive"))
    )
    (net (code "38") (name "Net-(IC2-CLK2)") (class "Default")
      (node (ref "IC2") (pin "6") (pinfunction "CLK2_6") (pintype "passive"))
      (node (ref "R52") (pin "1") (pinfunction "1_1") (pintype "passive"))
    )
    (net (code "39") (name "Net-(IC2-VDD)") (class "Default")
      (node (ref "C39") (pin "1") (pinfunction "1_1") (pintype "passive"))
      (node (ref "C40") (pin "1") (pinfunction "1_1") (pintype "passive"))
      (node (ref "FL2") (pin "2") (pinfunction "2_2") (pintype "passive"))
      (node (ref "IC2") (pin "1") (pinfunction "VDD_1") (pintype "passive"))
      (node (ref "IC2") (pin "7") (pinfunction "VDDO_7") (pintype "passive"))
    )
    (net (code "40") (name "Net-(IC2-XA)") (class "Default")
      (node (ref "IC2") (pin "2") (pinfunction "XA_2") (pintype "passive"))
      (node (ref "X1") (pin "2") (pinfunction "2_2") (pintype "passive"))
    )
    (net (code "41") (name "Net-(IC2-XB)") (class "Default")
      (node (ref "IC2") (pin "3") (pinfunction "XB_3") (pintype "passive"))
      (node (ref "X1") (pin "1") (pinfunction "1_1") (pintype "passive"))
    )
    (net (code "42") (name "Net-(J1-CC1)") (class "Default")
      (node (ref "J1") (pin "A5") (pinfunction "CC1_A5") (pintype "bidirectional"))
      (node (ref "R1") (pin "2") (pinfunction "2_2") (pintype "passive"))
    )
    (net (code "43") (name "Net-(J1-CC2)") (class "Default")
      (node (ref "J1") (pin "B5") (pinfunction "CC2_B5") (pintype "bidirectional"))
      (node (ref "R2") (pin "2") (pinfunction "2_2") (pintype "passive"))
    )
    (net (code "44") (name "Net-(J2-Pad2)") (class "Default")
      (node (ref "J2") (pin "2") (pinfunction "2_2") (pintype "passive"))
      (node (ref "R9") (pin "1") (pinfunction "1_1") (pintype "passive"))
    )
    (net (code "45") (name "Net-(J3-A1)") (class "Default")
      (node (ref "J3") (pin "1") (pinfunction "A1_1") (pintype "bidirectional"))
      (node (ref "R39") (pin "2") (pinfunction "2_2") (pintype "passive"))
    )
    (net (code "46") (name "Net-(J3-B2)") (class "Default")
      (node (ref "J3") (pin "2") (pinfunction "B2_2") (pintype "bidirectional"))
      (node (ref "R41") (pin "2") (pinfunction "2_2") (pintype "passive"))
    )
    (net (code "47") (name "Net-(J3-C3)") (class "Default")
      (node (ref "J3") (pin "3") (pinfunction "C3_3") (pintype "bidirectional"))
      (node (ref "R42") (pin "2") (pinfunction "2_2") (pintype "passive"))
    )
    (net (code "48") (name "Net-(J3-D5)") (class "Default")
      (node (ref "J3") (pin "5") (pinfunction "D5_5") (pintype "bidirectional"))
      (node (ref "R43") (pin "2") (pinfunction "2_2") (pintype "passive"))
    )
    (net (code "49") (name "Net-(J3-PUSH6)") (class "Default")
      (node (ref "J3") (pin "6") (pinfunction "PUSH6_6") (pintype "bidirectional"))
      (node (ref "R45") (pin "2") (pinfunction "2_2") (pintype "passive"))
    )
    (net (code "50") (name "Net-(R3-Pad1)") (class "Default")
      (node (ref "R3") (pin "1") (pinfunction "1_1") (pintype "passive"))
      (node (ref "R4") (pin "1") (pinfunction "1_1") (pintype "passive"))
    )
    (net (code "51") (name "Net-(R22-Pad1)") (class "Default")
      (node (ref "R22") (pin "1") (pinfunction "1_1") (pintype "passive"))
      (node (ref "R26") (pin "1") (pinfunction "1_1") (pintype "passive"))
    )
    (net (code "52") (name "Net-(U1-DPPM)") (class "Default")
      (node (ref "R16") (pin "2") (pinfunction "2_2") (pintype "passive"))
      (node (ref "U1") (pin "13") (pinfunction "DPPM_13") (pintype "passive"))
    )
    (net (code "53") (name "Net-(U1-TMR)") (class "Default")
      (node (ref "R28") (pin "2") (pinfunction "2_2") (pintype "passive"))
      (node (ref "U1") (pin "14") (pinfunction "TMR_14") (pintype "passive"))
    )
    (net (code "54") (name "Net-(U1-TS)") (class "Default")
      (node (ref "R9") (pin "2") (pinfunction "2_2") (pintype "passive"))
      (node (ref "U1") (pin "12") (pinfunction "TS_12") (pintype "passive"))
    )
    (net (code "55") (name "Net-(U1-VREF)") (class "Default")
      (node (ref "C14") (pin "1") (pinfunction "1_1") (pintype "passive"))
      (node (ref "U1") (pin "1") (pinfunction "VREF_1") (pintype "passive"))
    )
    (net (code "56") (name "Net-(U2-COMP1)") (class "Default")
      (node (ref "R5") (pin "2") (pinfunction "2_2") (pintype "passive"))
      (node (ref "U2") (pin "6") (pinfunction "COMP1_6") (pintype "passive"))
    )
    (net (code "57") (name "Net-(U2-COMP2)") (class "Default")
      (node (ref "R14") (pin "2") (pinfunction "2_2") (pintype "passive"))
      (node (ref "U2") (pin "10") (pinfunction "COMP2_10") (pintype "passive"))
    )
    (net (code "58") (name "Net-(U2-FB1)") (class "Default")
      (node (ref "R25") (pin "2") (pinfunction "2_2") (pintype "passive"))
      (node (ref "R4") (pin "2") (pinfunction "2_2") (pintype "passive"))
      (node (ref "U2") (pin "5") (pinfunction "FB1_5") (pintype "input"))
    )
    (net (code "59") (name "Net-(U2-FB2)") (class "Default")
      (node (ref "C21") (pin "1") (pinfunction "1_1") (pintype "passive"))
      (node (ref "R18") (pin "1") (pinfunction "1_1") (pintype "passive"))
      (node (ref "R22") (pin "2") (pinfunction "2_2") (pintype "passive"))
      (node (ref "U2") (pin "11") (pinfunction "FB2_11") (pintype "input"))
      (node (ref "U2") (pin "14") (pinfunction "VREG_14") (pintype "output"))
    )
    (net (code "60") (name "Net-(U2-INBK)") (class "Default")
      (node (ref "L1") (pin "1") (pinfunction "1_1") (pintype "passive"))
      (node (ref "U2") (pin "1") (pinfunction "INBK_1") (pintype "output"))
    )
    (net (code "61") (name "Net-(U2-SS)") (class "Default")
      (node (ref "R6") (pin "2") (pinfunction "2_2") (pintype "passive"))
      (node (ref "U2") (pin "8") (pinfunction "SS_8") (pintype "input"))
    )
    (net (code "62") (name "Net-(U2-SW1)") (class "Default")
      (node (ref "CR1") (pin "2") (pinfunction "2_2") (pintype "passive"))
      (node (ref "L1") (pin "2") (pinfunction "2_2") (pintype "passive"))
      (node (ref "U2") (pin "20") (pinfunction "SW1_20") (pintype "power_in"))
    )
    (net (code "63") (name "Net-(U2-SW2)") (class "Default")
      (node (ref "CR2") (pin "1") (pinfunction "1_1") (pintype "passive"))
      (node (ref "L2") (pin "1") (pinfunction "1_1") (pintype "passive"))
      (node (ref "U2") (pin "18") (pinfunction "SW2_18") (pintype "power_in"))
    )
    (net (code "64") (name "Net-(U2-VREF)") (class "Default")
      (node (ref "C13") (pin "1") (pinfunction "1_1") (pintype "passive"))
      (node (ref "R18") (pin "2") (pinfunction "2_2") (pintype "passive"))
      (node (ref "U2") (pin "12") (pinfunction "VREF_12") (pintype "output"))
    )
    (net (code "65") (name "Net-(U3-ILIM)") (class "Default")
      (node (ref "R21") (pin "2") (pinfunction "2_2") (pintype "passive"))
      (node (ref "U3") (pin "6") (pinfunction "ILIM_6") (pintype "passive"))
    )
    (net (code "66") (name "Net-(U3-SET)") (class "Default")
      (node (ref "C23") (pin "2") (pinfunction "2_2") (pintype "passive"))
      (node (ref "R27") (pin "2") (pinfunction "2_2") (pintype "passive"))
      (node (ref "U3") (pin "8") (pinfunction "SET_8") (pintype "passive"))
    )
    (net (code "67") (name "Net-(U4-ILIM)") (class "Default")
      (node (ref "R15") (pin "2") (pinfunction "2_2") (pintype "passive"))
      (node (ref "U4") (pin "5") (pinfunction "ILIM_5") (pintype "passive"))
    )
    (net (code "68") (name "Net-(U4-SET)") (class "Default")
      (node (ref "C18") (pin "2") (pinfunction "2_2") (pintype "passive"))
      (node (ref "R17") (pin "2") (pinfunction "2_2") (pintype "passive"))
      (node (ref "U4") (pin "7") (pinfunction "SET_7") (pintype "passive"))
    )
    (net (code "69") (name "Net-(U5-ILIM)") (class "Default")
      (node (ref "R19") (pin "2") (pinfunction "2_2") (pintype "passive"))
      (node (ref "U5") (pin "5") (pinfunction "ILIM_5") (pintype "passive"))
    )
    (net (code "70") (name "Net-(U5-PG)") (class "Default")
      (node (ref "R10") (pin "2") (pinfunction "2_2") (pintype "passive"))
      (node (ref "U5") (pin "4") (pinfunction "PG_4") (pintype "passive"))
    )
    (net (code "71") (name "Net-(U5-PGFB)") (class "Default")
      (node (ref "R23") (pin "2") (pinfunction "2_2") (pintype "passive"))
      (node (ref "R7") (pin "1") (pinfunction "1_1") (pintype "passive"))
      (node (ref "U5") (pin "6") (pinfunction "PGFB_6") (pintype "passive"))
    )
    (net (code "72") (name "Net-(U5-SET)") (class "Default")
      (node (ref "C15") (pin "2") (pinfunction "2_2") (pintype "passive"))
      (node (ref "R12") (pin "2") (pinfunction "2_2") (pintype "passive"))
      (node (ref "U5") (pin "7") (pinfunction "SET_7") (pintype "passive"))
    )
    (net (code "73") (name "Net-(U6-ILIM)") (class "Default")
      (node (ref "R20") (pin "2") (pinfunction "2_2") (pintype "passive"))
      (node (ref "U6") (pin "5") (pinfunction "ILIM_5") (pintype "passive"))
    )
    (net (code "74") (name "Net-(U6-PG)") (class "Default")
      (node (ref "R11") (pin "2") (pinfunction "2_2") (pintype "passive"))
      (node (ref "U6") (pin "4") (pinfunction "PG_4") (pintype "passive"))
    )
    (net (code "75") (name "Net-(U6-PGFB)") (class "Default")
      (node (ref "R24") (pin "2") (pinfunction "2_2") (pintype "passive"))
      (node (ref "R8") (pin "1") (pinfunction "1_1") (pintype "passive"))
      (node (ref "U6") (pin "6") (pinfunction "PGFB_6") (pintype "passive"))
    )
    (net (code "76") (name "Net-(U6-SET)") (class "Default")
      (node (ref "C16") (pin "2") (pinfunction "2_2") (pintype "passive"))
      (node (ref "R13") (pin "2") (pinfunction "2_2") (pintype "passive"))
      (node (ref "U6") (pin "7") (pinfunction "SET_7") (pintype "passive"))
    )
    (net (code "77") (name "Net-(U7-EN)") (class "Default")
      (node (ref "D1") (pin "3") (pinfunction "3_3") (pintype "passive"))
      (node (ref "R30") (pin "2") (pinfunction "2_2") (pintype "passive"))
      (node (ref "U7") (pin "3") (pinfunction "EN_3") (pintype "input"))
    )
    (net (code "78") (name "Net-(U8-BOOT0)") (class "Default")
      (node (ref "R31") (pin "1") (pinfunction "1_1") (pintype "passive"))
      (node (ref "U8") (pin "60") (pinfunction "BOOT0_60") (pintype "passive"))
    )
    (net (code "79") (name "Net-(U8-NRST)") (class "Default")
      (node (ref "C27") (pin "1") (pinfunction "1_1") (pintype "passive"))
      (node (ref "U8") (pin "7") (pinfunction "NRST_7") (pintype "passive"))
    )
    (net (code "80") (name "Net-(U8-PB6)") (class "Default")
      (node (ref "R34") (pin "1") (pinfunction "1_1") (pintype "passive"))
      (node (ref "R36") (pin "2") (pinfunction "2_2") (pintype "passive"))
      (node (ref "U8") (pin "58") (pinfunction "PB6_58") (pintype "passive"))
    )
    (net (code "81") (name "Net-(U8-PB7)") (class "Default")
      (node (ref "R32") (pin "1") (pinfunction "1_1") (pintype "passive"))
      (node (ref "R35") (pin "2") (pinfunction "2_2") (pintype "passive"))
      (node (ref "U8") (pin "59") (pinfunction "PB7_59") (pintype "passive"))
    )
    (net (code "82") (name "Net-(U8-PB12)") (class "Default")
      (node (ref "R48") (pin "1") (pinfunction "1_1") (pintype "passive"))
      (node (ref "U8") (pin "33") (pinfunction "PB12_33") (pintype "passive"))
    )
    (net (code "83") (name "Net-(U8-PB13)") (class "Default")
      (node (ref "R47") (pin "1") (pinfunction "1_1") (pintype "passive"))
      (node (ref "U8") (pin "34") (pinfunction "PB13_34") (pintype "passive"))
    )
    (net (code "84") (name "Net-(U8-PC3)") (class "Default")
      (node (ref "R37") (pin "2") (pinfunction "2_2") (pintype "passive"))
      (node (ref "U8") (pin "11") (pinfunction "PC3_11") (pintype "passive"))
    )
    (net (code "85") (name "Net-(U8-VDDA{slash}VREF+)") (class "Default")
      (node (ref "C30") (pin "1") (pinfunction "1_1") (pintype "passive"))
      (node (ref "C31") (pin "1") (pinfunction "1_1") (pintype "passive"))
      (node (ref "FL1") (pin "2") (pinfunction "2_2") (pintype "passive"))
      (node (ref "U8") (pin "13") (pinfunction "VDDA/VREF+_13") (pintype "passive"))
    )
    (net (code "86") (name "Net-(U9-+INA)") (class "Default")
      (node (ref "C37") (pin "2") (pinfunction "2_2") (pintype "passive"))
      (node (ref "R44") (pin "2") (pinfunction "2_2") (pintype "passive"))
      (node (ref "R50") (pin "2") (pinfunction "2_2") (pintype "passive"))
      (node (ref "U9") (pin "1") (pinfunction "+INA_1") (pintype "input"))
    )
    (net (code "87") (name "Net-(U9-+INB)") (class "Default")
      (node (ref "C36") (pin "2") (pinfunction "2_2") (pintype "passive"))
      (node (ref "R46") (pin "2") (pinfunction "2_2") (pintype "passive"))
      (node (ref "R49") (pin "2") (pinfunction "2_2") (pintype "passive"))
      (node (ref "U9") (pin "5") (pinfunction "+INB_5") (pintype "input"))
    )
    (net (code "88") (name "Net-(U9--INA)") (class "Default")
      (node (ref "C25") (pin "1") (pinfunction "1_1") (pintype "passive"))
      (node (ref "R29") (pin "1") (pinfunction "1_1") (pintype "passive"))
      (node (ref "R38") (pin "2") (pinfunction "2_2") (pintype "passive"))
      (node (ref "U9") (pin "10") (pinfunction "-INA_10") (pintype "input"))
    )
    (net (code "89") (name "Net-(U9--INB)") (class "Default")
      (node (ref "C28") (pin "1") (pinfunction "1_1") (pintype "passive"))
      (node (ref "R33") (pin "1") (pinfunction "1_1") (pintype "passive"))
      (node (ref "R40") (pin "2") (pinfunction "2_2") (pintype "passive"))
      (node (ref "U9") (pin "6") (pinfunction "-INB_6") (pintype "input"))
    )
    (net (code "90") (name "Net-(U9-OUTA)") (class "Default")
      (node (ref "C28") (pin "2") (pinfunction "2_2") (pintype "passive"))
      (node (ref "C29") (pin "1") (pinfunction "1_1") (pintype "passive"))
      (node (ref "R33") (pin "2") (pinfunction "2_2") (pintype "passive"))
      (node (ref "U9") (pin "9") (pinfunction "OUTA_9") (pintype "output"))
    )
    (net (code "91") (name "Net-(U9-OUTB)") (class "Default")
      (node (ref "C25") (pin "2") (pinfunction "2_2") (pintype "passive"))
      (node (ref "C32") (pin "1") (pinfunction "1_1") (pintype "passive"))
      (node (ref "R29") (pin "2") (pinfunction "2_2") (pintype "passive"))
      (node (ref "U9") (pin "7") (pinfunction "OUTB_7") (pintype "output"))
    )
    (net (code "92") (name "unconnected-(IC1-BIAS-Pad4)") (class "Default")
      (node (ref "IC1") (pin "4") (pinfunction "BIAS_4") (pintype "passive"))
    )
    (net (code "93") (name "unconnected-(IC1-FSYNC-Pad6)") (class "Default")
      (node (ref "IC1") (pin "6") (pinfunction "FSYNC_6") (pintype "passive"))
    )
    (net (code "94") (name "unconnected-(IC1-GPIO1-Pad17)") (class "Default")
      (node (ref "IC1") (pin "17") (pinfunction "GPIO1_17") (pintype "passive"))
    )
    (net (code "95") (name "unconnected-(IC1-GPIO2-Pad16)") (class "Default")
      (node (ref "IC1") (pin "16") (pinfunction "GPIO2_16") (pintype "passive"))
    )
    (net (code "96") (name "unconnected-(IC1-NC-Pad26)") (class "Default")
      (node (ref "IC1") (pin "26") (pinfunction "NC_26") (pintype "passive"))
    )
    (net (code "97") (name "unconnected-(IC1-SW-Pad5)") (class "Default")
      (node (ref "IC1") (pin "5") (pinfunction "SW_5") (pintype "passive"))
    )
    (net (code "98") (name "unconnected-(IC1-XOUT-Pad28)") (class "Default")
      (node (ref "IC1") (pin "28") (pinfunction "XOUT_28") (pintype "passive"))
    )
    (net (code "99") (name "unconnected-(IC2-CLK1-Pad9)") (class "Default")
      (node (ref "IC2") (pin "9") (pinfunction "CLK1_9") (pintype "passive"))
    )
    (net (code "100") (name "unconnected-(J1-SBU1-PadA8)") (class "Default")
      (node (ref "J1") (pin "A8") (pinfunction "SBU1_A8") (pintype "bidirectional"))
    )
    (net (code "101") (name "unconnected-(J1-SBU2-PadB8)") (class "Default")
      (node (ref "J1") (pin "B8") (pinfunction "SBU2_B8") (pintype "bidirectional"))
    )
    (net (code "102") (name "unconnected-(U1-EP-Pad21)") (class "Default")
      (node (ref "U1") (pin "21") (pinfunction "EP_21") (pintype "passive"))
    )
    (net (code "103") (name "unconnected-(U1-ISET1-Pad10)") (class "Default")
      (node (ref "U1") (pin "10") (pinfunction "ISET1_10") (pintype "passive"))
    )
    (net (code "104") (name "unconnected-(U1-ISET2-Pad7)") (class "Default")
      (node (ref "U1") (pin "7") (pinfunction "ISET2_7") (pintype "passive"))
    )
    (net (code "105") (name "unconnected-(U1-PG-Pad18)") (class "Default")
      (node (ref "U1") (pin "18") (pinfunction "PG_18") (pintype "passive"))
    )
    (net (code "106") (name "unconnected-(U1-STAT1-Pad2)") (class "Default")
      (node (ref "U1") (pin "2") (pinfunction "STAT1_2") (pintype "passive"))
    )
    (net (code "107") (name "unconnected-(U1-STAT2-Pad3)") (class "Default")
      (node (ref "U1") (pin "3") (pinfunction "STAT2_3") (pintype "passive"))
    )
    (net (code "108") (name "unconnected-(U1-VSS-Pad11)") (class "Default")
      (node (ref "U1") (pin "11") (pinfunction "VSS_11") (pintype "passive"))
    )
    (net (code "109") (name "unconnected-(U2-SEQ-Pad3)") (class "Default")
      (node (ref "U2") (pin "3") (pinfunction "SEQ_3") (pintype "passive"))
    )
    (net (code "110") (name "unconnected-(U2-SLEW-Pad4)") (class "Default")
      (node (ref "U2") (pin "4") (pinfunction "SLEW_4") (pintype "passive"))
    )
    (net (code "111") (name "unconnected-(U3-PG-Pad4)") (class "Default")
      (node (ref "U3") (pin "4") (pinfunction "PG_4") (pintype "output"))
    )
    (net (code "112") (name "unconnected-(U3-VIOC-Pad7)") (class "Default")
      (node (ref "U3") (pin "7") (pinfunction "VIOC_7") (pintype "power_in"))
    )
    (net (code "113") (name "unconnected-(U4-PG-Pad4)") (class "Default")
      (node (ref "U4") (pin "4") (pinfunction "PG_4") (pintype "passive"))
    )
    (net (code "114") (name "unconnected-(U8-PA0-Pad14)") (class "Default")
      (node (ref "U8") (pin "14") (pinfunction "PA0_14") (pintype "passive"))
    )
    (net (code "115") (name "unconnected-(U8-PA1-Pad15)") (class "Default")
      (node (ref "U8") (pin "15") (pinfunction "PA1_15") (pintype "passive"))
    )
    (net (code "116") (name "unconnected-(U8-PA2-Pad16)") (class "Default")
      (node (ref "U8") (pin "16") (pinfunction "PA2_16") (pintype "passive"))
    )
    (net (code "117") (name "unconnected-(U8-PA3-Pad17)") (class "Default")
      (node (ref "U8") (pin "17") (pinfunction "PA3_17") (pintype "passive"))
    )
    (net (code "118") (name "unconnected-(U8-PA8-Pad41)") (class "Default")
      (node (ref "U8") (pin "41") (pinfunction "PA8_41") (pintype "passive"))
    )
    (net (code "119") (name "unconnected-(U8-PA9-Pad42)") (class "Default")
      (node (ref "U8") (pin "42") (pinfunction "PA9_42") (pintype "passive"))
    )
    (net (code "120") (name "unconnected-(U8-PA10-Pad43)") (class "Default")
      (node (ref "U8") (pin "43") (pinfunction "PA10_43") (pintype "passive"))
    )
    (net (code "121") (name "unconnected-(U8-PA13-Pad46)") (class "Default")
      (node (ref "U8") (pin "46") (pinfunction "PA13_46") (pintype "passive"))
    )
    (net (code "122") (name "unconnected-(U8-PA15-Pad50)") (class "Default")
      (node (ref "U8") (pin "50") (pinfunction "PA15_50") (pintype "passive"))
    )
    (net (code "123") (name "unconnected-(U8-PB0-Pad26)") (class "Default")
      (node (ref "U8") (pin "26") (pinfunction "PB0_26") (pintype "passive"))
    )
    (net (code "124") (name "unconnected-(U8-PB1-Pad27)") (class "Default")
      (node (ref "U8") (pin "27") (pinfunction "PB1_27") (pintype "passive"))
    )
    (net (code "125") (name "unconnected-(U8-PB2-Pad28)") (class "Default")
      (node (ref "U8") (pin "28") (pinfunction "PB2_28") (pintype "passive"))
    )
    (net (code "126") (name "unconnected-(U8-PB3-Pad55)") (class "Default")
      (node (ref "U8") (pin "55") (pinfunction "PB3_55") (pintype "passive"))
    )
    (net (code "127") (name "unconnected-(U8-PB4-Pad56)") (class "Default")
      (node (ref "U8") (pin "56") (pinfunction "PB4_56") (pintype "passive"))
    )
    (net (code "128") (name "unconnected-(U8-PB5-Pad57)") (class "Default")
      (node (ref "U8") (pin "57") (pinfunction "PB5_57") (pintype "passive"))
    )
    (net (code "129") (name "unconnected-(U8-PB8-Pad61)") (class "Default")
      (node (ref "U8") (pin "61") (pinfunction "PB8_61") (pintype "passive"))
    )
    (net (code "130") (name "unconnected-(U8-PB9-Pad62)") (class "Default")
      (node (ref "U8") (pin "62") (pinfunction "PB9_62") (pintype "passive"))
    )
    (net (code "131") (name "unconnected-(U8-PB10-Pad29)") (class "Default")
      (node (ref "U8") (pin "29") (pinfunction "PB10_29") (pintype "passive"))
    )
    (net (code "132") (name "unconnected-(U8-PB14-Pad35)") (class "Default")
      (node (ref "U8") (pin "35") (pinfunction "PB14_35") (pintype "passive"))
    )
    (net (code "133") (name "unconnected-(U8-PB15-Pad36)") (class "Default")
      (node (ref "U8") (pin "36") (pinfunction "PB15_36") (pintype "passive"))
    )
    (net (code "134") (name "unconnected-(U8-PC0-Pad8)") (class "Default")
      (node (ref "U8") (pin "8") (pinfunction "PC0_8") (pintype "passive"))
    )
    (net (code "135") (name "unconnected-(U8-PC1-Pad9)") (class "Default")
      (node (ref "U8") (pin "9") (pinfunction "PC1_9") (pintype "passive"))
    )
    (net (code "136") (name "unconnected-(U8-PC6-Pad37)") (class "Default")
      (node (ref "U8") (pin "37") (pinfunction "PC6_37") (pintype "passive"))
    )
    (net (code "137") (name "unconnected-(U8-PC7-Pad38)") (class "Default")
      (node (ref "U8") (pin "38") (pinfunction "PC7_38") (pintype "passive"))
    )
    (net (code "138") (name "unconnected-(U8-PC10-Pad51)") (class "Default")
      (node (ref "U8") (pin "51") (pinfunction "PC10_51") (pintype "passive"))
    )
    (net (code "139") (name "unconnected-(U8-PC11-Pad52)") (class "Default")
      (node (ref "U8") (pin "52") (pinfunction "PC11_52") (pintype "passive"))
    )
    (net (code "140") (name "unconnected-(U8-PC12-Pad53)") (class "Default")
      (node (ref "U8") (pin "53") (pinfunction "PC12_53") (pintype "passive"))
    )
    (net (code "141") (name "unconnected-(U8-PC13-Pad2)") (class "Default")
      (node (ref "U8") (pin "2") (pinfunction "PC13_2") (pintype "passive"))
    )
    (net (code "142") (name "unconnected-(U8-PC14-OSC32_IN-Pad3)") (class "Default")
      (node (ref "U8") (pin "3") (pinfunction "PC14-OSC32_IN_3") (pintype "passive"))
    )
    (net (code "143") (name "unconnected-(U8-PC15-OSC32_OUT-Pad4)") (class "Default")
      (node (ref "U8") (pin "4") (pinfunction "PC15-OSC32_OUT_4") (pintype "passive"))
    )
    (net (code "144") (name "unconnected-(U8-PD2-Pad54)") (class "Default")
      (node (ref "U8") (pin "54") (pinfunction "PD2_54") (pintype "passive"))
    )
    (net (code "145") (name "unconnected-(U8-PH1-OSC_OUT-Pad6)") (class "Default")
      (node (ref "U8") (pin "6") (pinfunction "PH1-OSC_OUT_6") (pintype "passive"))
    )
    (net (code "146") (name "unconnected-(U8-VCAP_1-Pad30)") (class "Default")
      (node (ref "U8") (pin "30") (pinfunction "VCAP_1_30") (pintype "passive"))
    )
    (net (code "147") (name "unconnected-(U8-VSS-Pad18)") (class "Default")
      (node (ref "U8") (pin "18") (pinfunction "VSS_18") (pintype "passive"))
    )
  )
)
